# old_eagle_line_sensor.net
KiCad netlist of a schematic drawn in EAGLE
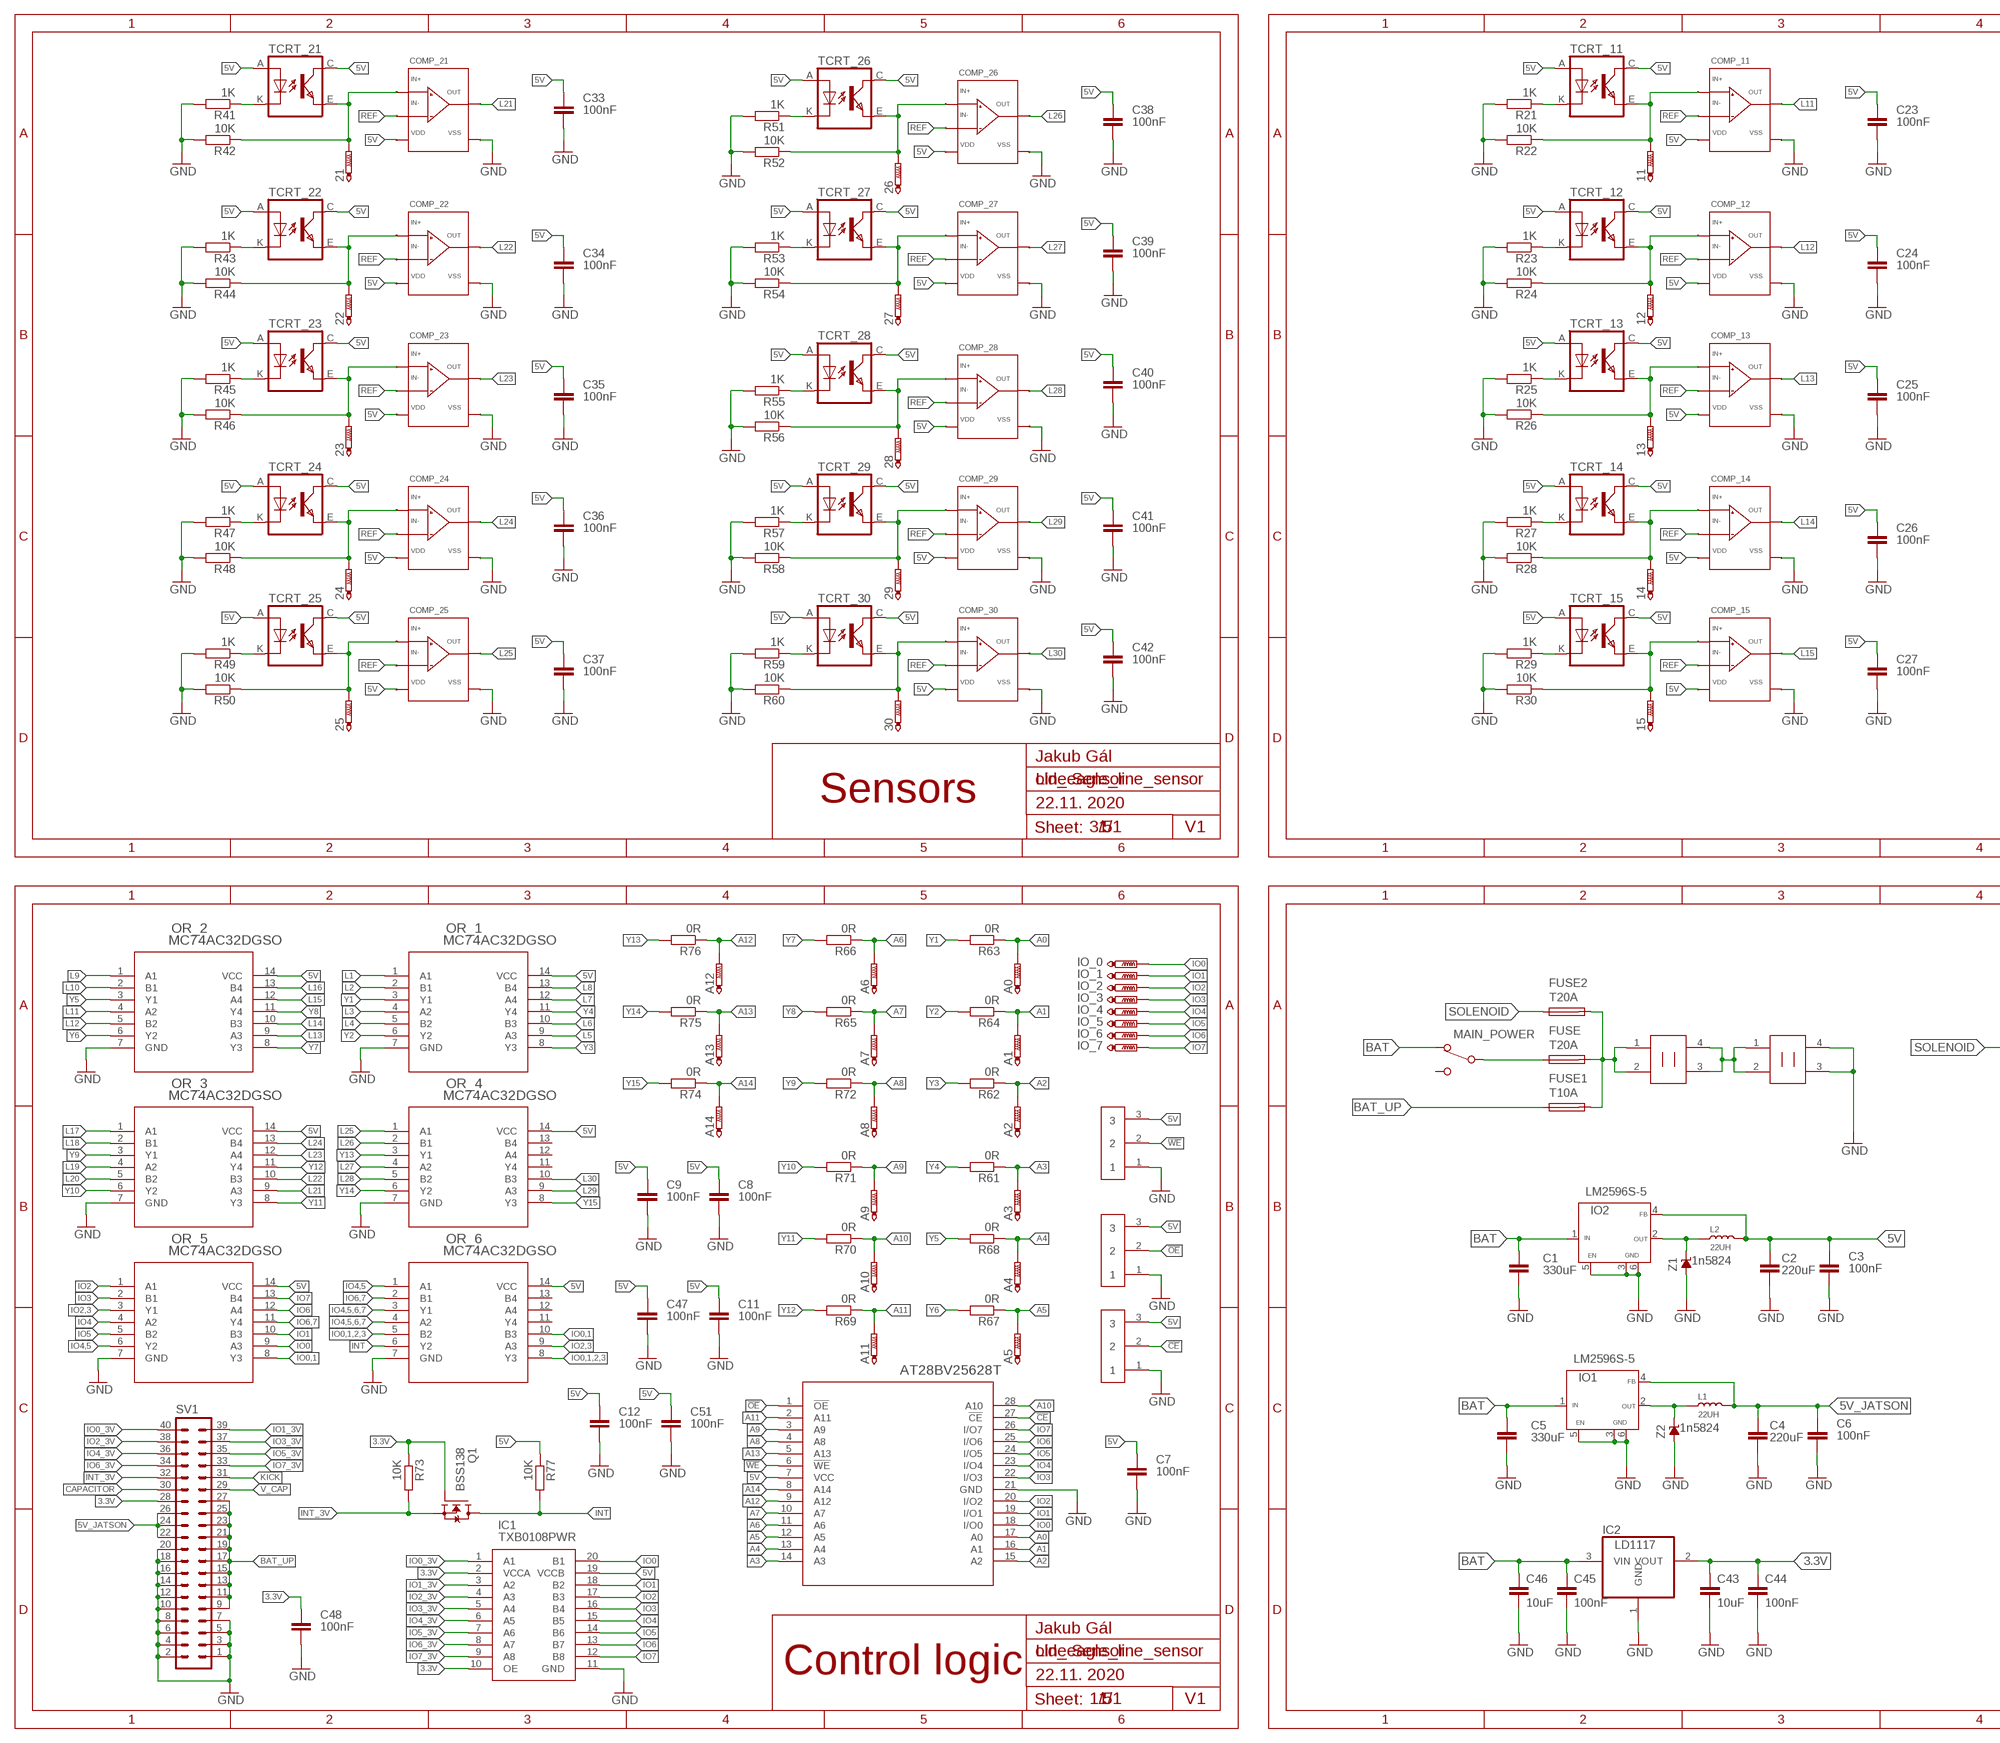
[diagram p0: schematic, sheet 1, part 1 of 2]
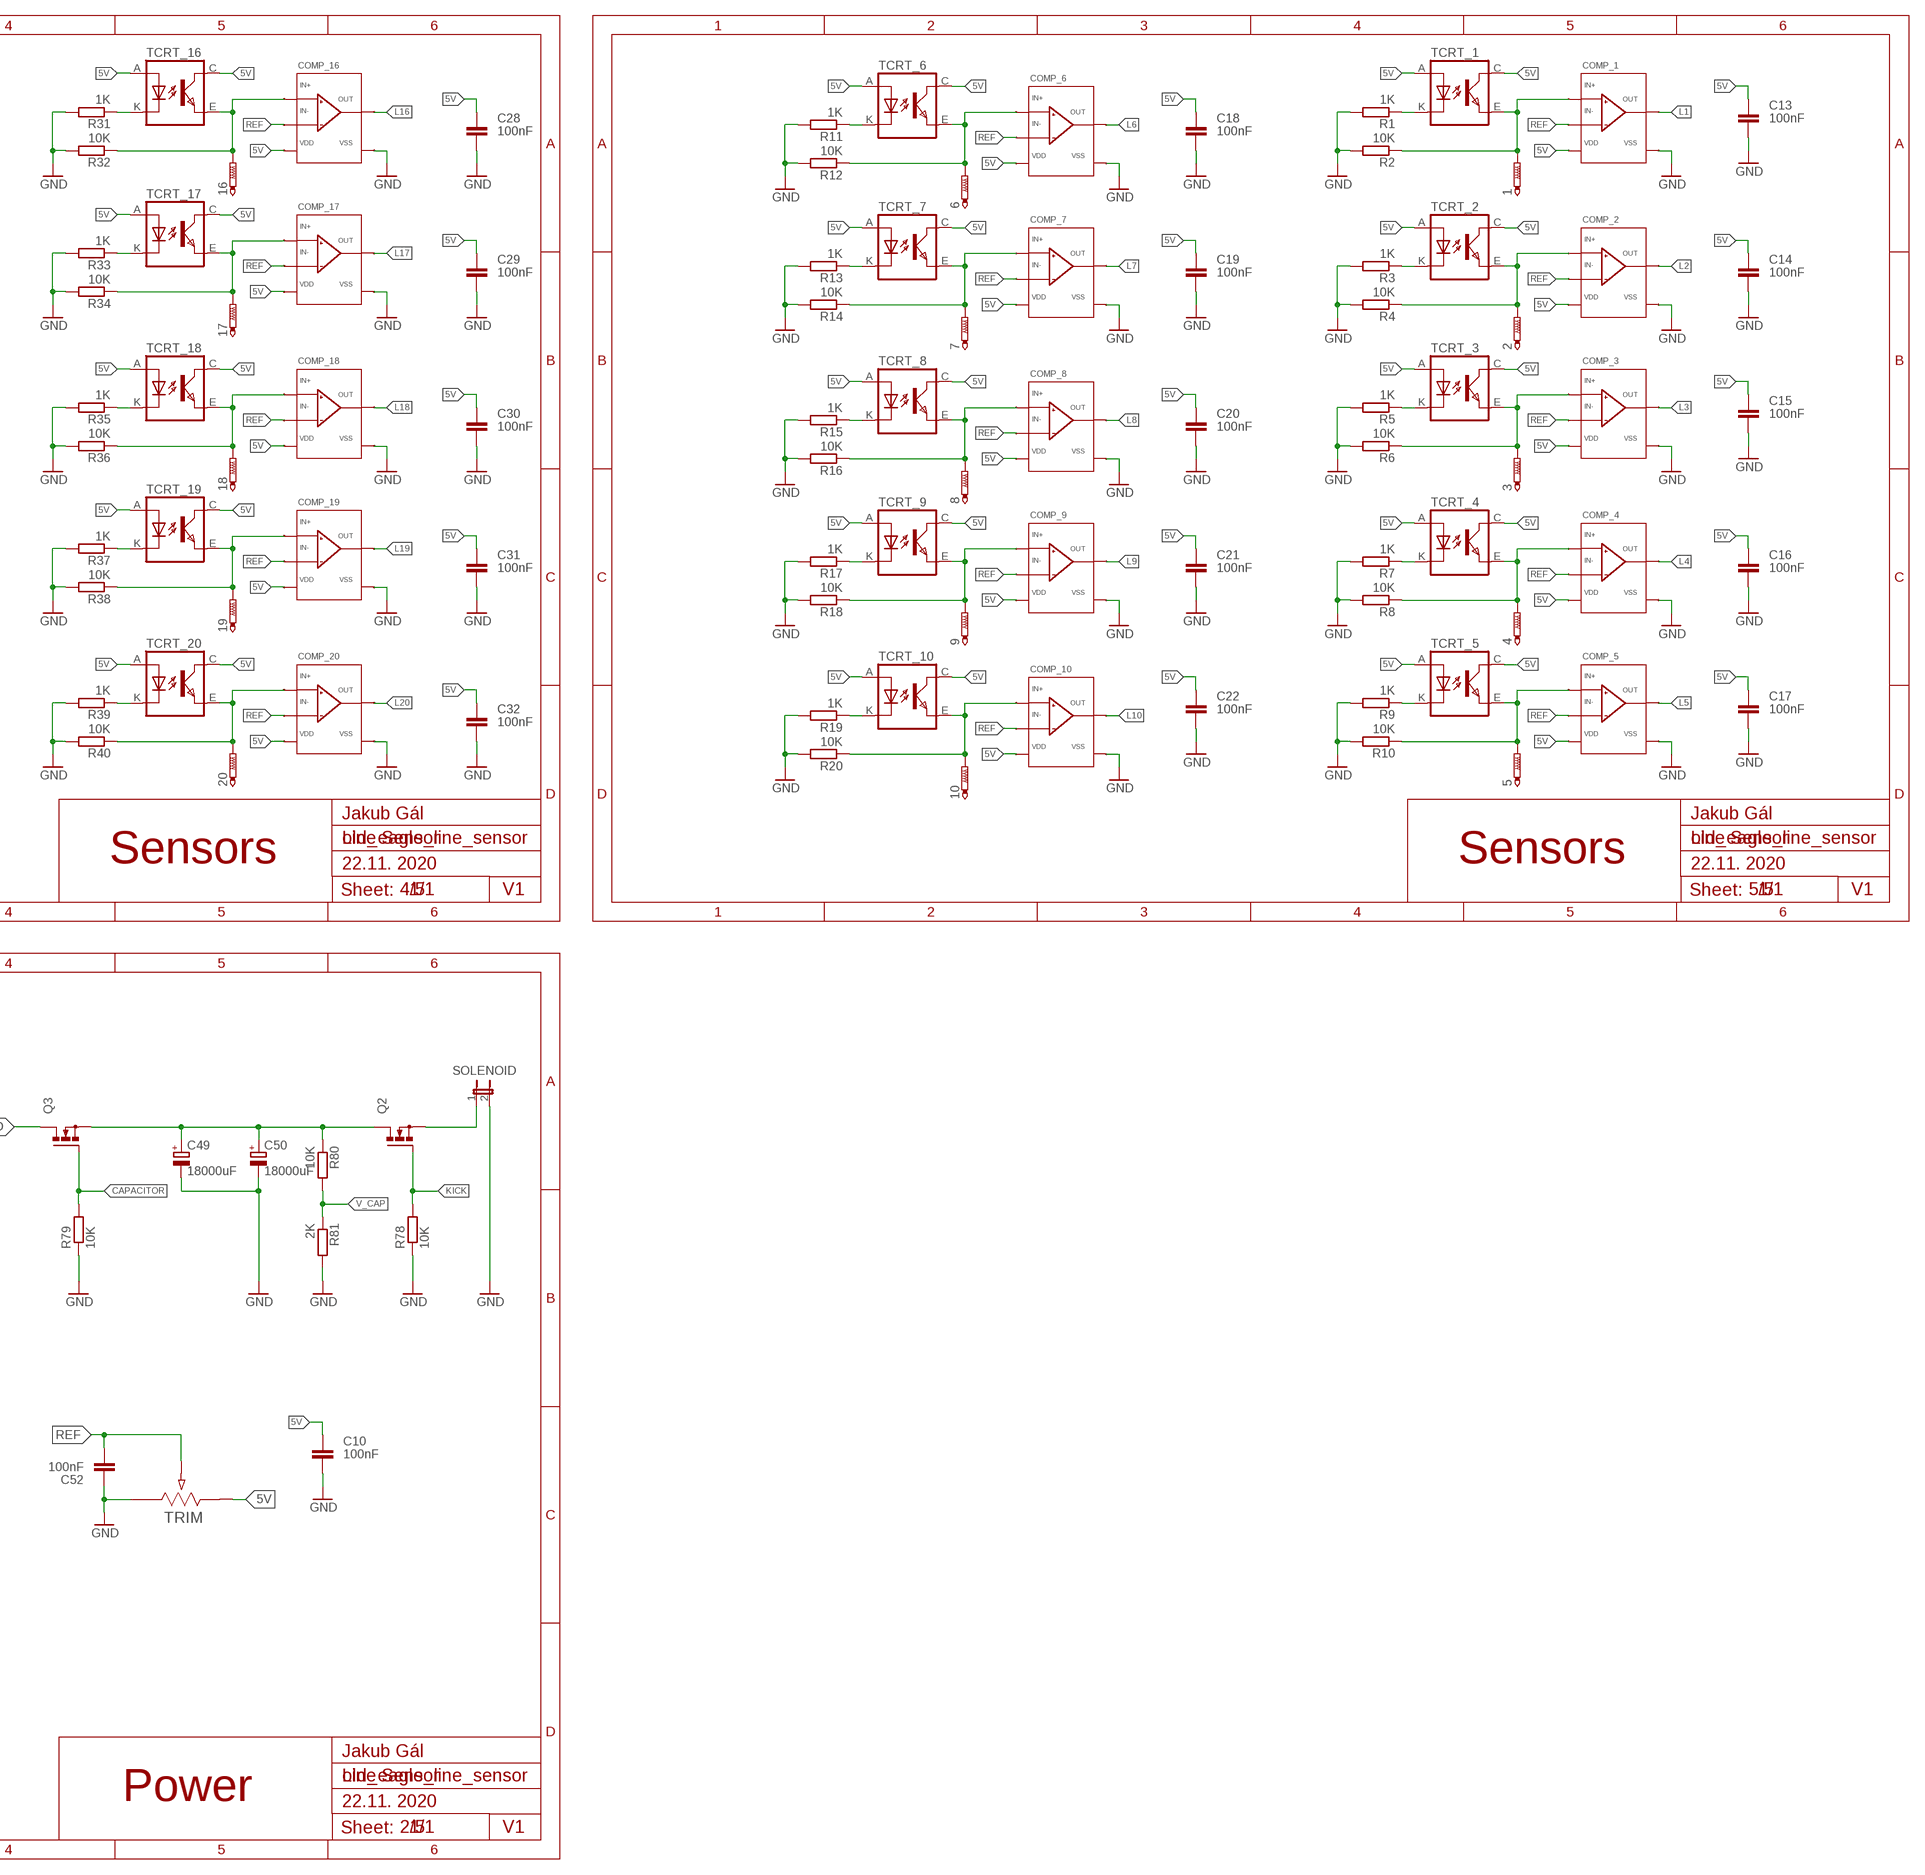
[diagram p1: schematic, sheet 1, part 2 of 2]

(export (version "E")
  (design (tool "Eeschema 10.0.6"))
  (components
    (comp (ref "!CE")
      (value "0603_S")
      (footprint "eagle-import:0603_S")
      (libsource (lib "eagle-import") (part "0603_S"))
    )
    (comp (ref "!OE")
      (value "0603_S")
      (footprint "eagle-import:0603_S")
      (libsource (lib "eagle-import") (part "0603_S"))
    )
    (comp (ref "!WE")
      (value "0603_S")
      (footprint "eagle-import:0603_S")
      (libsource (lib "eagle-import") (part "0603_S"))
    )
    (comp (ref "1")
      (value "PTR1TP20R")
      (footprint "eagle-import:TP20R")
      (libsource (lib "eagle-import") (part "PTR1TP20R"))
    )
    (comp (ref "2")
      (value "PTR1TP20R")
      (footprint "eagle-import:TP20R")
      (libsource (lib "eagle-import") (part "PTR1TP20R"))
    )
    (comp (ref "3")
      (value "PTR1TP20R")
      (footprint "eagle-import:TP20R")
      (libsource (lib "eagle-import") (part "PTR1TP20R"))
    )
    (comp (ref "4")
      (value "PTR1TP20R")
      (footprint "eagle-import:TP20R")
      (libsource (lib "eagle-import") (part "PTR1TP20R"))
    )
    (comp (ref "5")
      (value "PTR1TP20R")
      (footprint "eagle-import:TP20R")
      (libsource (lib "eagle-import") (part "PTR1TP20R"))
    )
    (comp (ref "6")
      (value "PTR1TP20R")
      (footprint "eagle-import:TP20R")
      (libsource (lib "eagle-import") (part "PTR1TP20R"))
    )
    (comp (ref "7")
      (value "PTR1TP20R")
      (footprint "eagle-import:TP20R")
      (libsource (lib "eagle-import") (part "PTR1TP20R"))
    )
    (comp (ref "8")
      (value "PTR1TP20R")
      (footprint "eagle-import:TP20R")
      (libsource (lib "eagle-import") (part "PTR1TP20R"))
    )
    (comp (ref "9")
      (value "PTR1TP20R")
      (footprint "eagle-import:TP20R")
      (libsource (lib "eagle-import") (part "PTR1TP20R"))
    )
    (comp (ref "10")
      (value "PTR1TP20R")
      (footprint "eagle-import:TP20R")
      (libsource (lib "eagle-import") (part "PTR1TP20R"))
    )
    (comp (ref "11")
      (value "PTR1TP20R")
      (footprint "eagle-import:TP20R")
      (libsource (lib "eagle-import") (part "PTR1TP20R"))
    )
    (comp (ref "12")
      (value "PTR1TP20R")
      (footprint "eagle-import:TP20R")
      (libsource (lib "eagle-import") (part "PTR1TP20R"))
    )
    (comp (ref "13")
      (value "PTR1TP20R")
      (footprint "eagle-import:TP20R")
      (libsource (lib "eagle-import") (part "PTR1TP20R"))
    )
    (comp (ref "14")
      (value "PTR1TP20R")
      (footprint "eagle-import:TP20R")
      (libsource (lib "eagle-import") (part "PTR1TP20R"))
    )
    (comp (ref "15")
      (value "PTR1TP20R")
      (footprint "eagle-import:TP20R")
      (libsource (lib "eagle-import") (part "PTR1TP20R"))
    )
    (comp (ref "16")
      (value "PTR1TP20R")
      (footprint "eagle-import:TP20R")
      (libsource (lib "eagle-import") (part "PTR1TP20R"))
    )
    (comp (ref "17")
      (value "PTR1TP20R")
      (footprint "eagle-import:TP20R")
      (libsource (lib "eagle-import") (part "PTR1TP20R"))
    )
    (comp (ref "18")
      (value "PTR1TP20R")
      (footprint "eagle-import:TP20R")
      (libsource (lib "eagle-import") (part "PTR1TP20R"))
    )
    (comp (ref "19")
      (value "PTR1TP20R")
      (footprint "eagle-import:TP20R")
      (libsource (lib "eagle-import") (part "PTR1TP20R"))
    )
    (comp (ref "20")
      (value "PTR1TP20R")
      (footprint "eagle-import:TP20R")
      (libsource (lib "eagle-import") (part "PTR1TP20R"))
    )
    (comp (ref "21")
      (value "PTR1TP20R")
      (footprint "eagle-import:TP20R")
      (libsource (lib "eagle-import") (part "PTR1TP20R"))
    )
    (comp (ref "22")
      (value "PTR1TP20R")
      (footprint "eagle-import:TP20R")
      (libsource (lib "eagle-import") (part "PTR1TP20R"))
    )
    (comp (ref "23")
      (value "PTR1TP20R")
      (footprint "eagle-import:TP20R")
      (libsource (lib "eagle-import") (part "PTR1TP20R"))
    )
    (comp (ref "24")
      (value "PTR1TP20R")
      (footprint "eagle-import:TP20R")
      (libsource (lib "eagle-import") (part "PTR1TP20R"))
    )
    (comp (ref "25")
      (value "PTR1TP20R")
      (footprint "eagle-import:TP20R")
      (libsource (lib "eagle-import") (part "PTR1TP20R"))
    )
    (comp (ref "26")
      (value "PTR1TP20R")
      (footprint "eagle-import:TP20R")
      (libsource (lib "eagle-import") (part "PTR1TP20R"))
    )
    (comp (ref "27")
      (value "PTR1TP20R")
      (footprint "eagle-import:TP20R")
      (libsource (lib "eagle-import") (part "PTR1TP20R"))
    )
    (comp (ref "28")
      (value "PTR1TP20R")
      (footprint "eagle-import:TP20R")
      (libsource (lib "eagle-import") (part "PTR1TP20R"))
    )
    (comp (ref "29")
      (value "PTR1TP20R")
      (footprint "eagle-import:TP20R")
      (libsource (lib "eagle-import") (part "PTR1TP20R"))
    )
    (comp (ref "30")
      (value "PTR1TP20R")
      (footprint "eagle-import:TP20R")
      (libsource (lib "eagle-import") (part "PTR1TP20R"))
    )
    (comp (ref "A0")
      (value "PTR1TP20R")
      (footprint "eagle-import:TP20R")
      (libsource (lib "eagle-import") (part "PTR1TP20R"))
    )
    (comp (ref "A1")
      (value "PTR1TP20R")
      (footprint "eagle-import:TP20R")
      (libsource (lib "eagle-import") (part "PTR1TP20R"))
    )
    (comp (ref "A2")
      (value "PTR1TP20R")
      (footprint "eagle-import:TP20R")
      (libsource (lib "eagle-import") (part "PTR1TP20R"))
    )
    (comp (ref "A3")
      (value "PTR1TP20R")
      (footprint "eagle-import:TP20R")
      (libsource (lib "eagle-import") (part "PTR1TP20R"))
    )
    (comp (ref "A4")
      (value "PTR1TP20R")
      (footprint "eagle-import:TP20R")
      (libsource (lib "eagle-import") (part "PTR1TP20R"))
    )
    (comp (ref "A5")
      (value "PTR1TP20R")
      (footprint "eagle-import:TP20R")
      (libsource (lib "eagle-import") (part "PTR1TP20R"))
    )
    (comp (ref "A6")
      (value "PTR1TP20R")
      (footprint "eagle-import:TP20R")
      (libsource (lib "eagle-import") (part "PTR1TP20R"))
    )
    (comp (ref "A7")
      (value "PTR1TP20R")
      (footprint "eagle-import:TP20R")
      (libsource (lib "eagle-import") (part "PTR1TP20R"))
    )
    (comp (ref "A8")
      (value "PTR1TP20R")
      (footprint "eagle-import:TP20R")
      (libsource (lib "eagle-import") (part "PTR1TP20R"))
    )
    (comp (ref "A9")
      (value "PTR1TP20R")
      (footprint "eagle-import:TP20R")
      (libsource (lib "eagle-import") (part "PTR1TP20R"))
    )
    (comp (ref "A10")
      (value "PTR1TP20R")
      (footprint "eagle-import:TP20R")
      (libsource (lib "eagle-import") (part "PTR1TP20R"))
    )
    (comp (ref "A11")
      (value "PTR1TP20R")
      (footprint "eagle-import:TP20R")
      (libsource (lib "eagle-import") (part "PTR1TP20R"))
    )
    (comp (ref "A12")
      (value "PTR1TP20R")
      (footprint "eagle-import:TP20R")
      (libsource (lib "eagle-import") (part "PTR1TP20R"))
    )
    (comp (ref "A13")
      (value "PTR1TP20R")
      (footprint "eagle-import:TP20R")
      (libsource (lib "eagle-import") (part "PTR1TP20R"))
    )
    (comp (ref "A14")
      (value "PTR1TP20R")
      (footprint "eagle-import:TP20R")
      (libsource (lib "eagle-import") (part "PTR1TP20R"))
    )
    (comp (ref "AT28BV25628T")
      (value "AT28BV25628T_ATM-M")
      (footprint "eagle-import:28T_ATM-M")
      (fields (field (name "MANUFACTURER_PART_NUMBER") "AT28BV256-20TU"))
      (libsource (lib "eagle-import") (part "AT28BV25628T_ATM-M"))
    )
    (comp (ref "C1")
      (value "330uF")
      (footprint "eagle-import:CAPM7343X310")
      (libsource (lib "eagle-import") (part "CTANTALUM-2917(7343-METRIC)_"))
    )
    (comp (ref "C2")
      (value "220uF")
      (footprint "eagle-import:CAPM7343X310")
      (libsource (lib "eagle-import") (part "CTANTALUM-2917(7343-METRIC)_"))
    )
    (comp (ref "C3")
      (value "100nF")
      (footprint "eagle-import:C0603")
      (libsource (lib "eagle-import") (part "C-EUC0603"))
    )
    (comp (ref "C4")
      (value "220uF")
      (footprint "eagle-import:CAPM7343X310")
      (libsource (lib "eagle-import") (part "CTANTALUM-2917(7343-METRIC)_"))
    )
    (comp (ref "C5")
      (value "330uF")
      (footprint "eagle-import:CAPM7343X310")
      (libsource (lib "eagle-import") (part "CTANTALUM-2917(7343-METRIC)_"))
    )
    (comp (ref "C6")
      (value "100nF")
      (footprint "eagle-import:C0603")
      (libsource (lib "eagle-import") (part "C-EUC0603"))
    )
    (comp (ref "C7")
      (value "100nF")
      (footprint "eagle-import:C0603")
      (libsource (lib "eagle-import") (part "C-EUC0603"))
    )
    (comp (ref "C8")
      (value "100nF")
      (footprint "eagle-import:C0603")
      (libsource (lib "eagle-import") (part "C-EUC0603"))
    )
    (comp (ref "C9")
      (value "100nF")
      (footprint "eagle-import:C0603")
      (libsource (lib "eagle-import") (part "C-EUC0603"))
    )
    (comp (ref "C10")
      (value "100nF")
      (footprint "eagle-import:C0603")
      (libsource (lib "eagle-import") (part "C-EUC0603"))
    )
    (comp (ref "C11")
      (value "100nF")
      (footprint "eagle-import:C0603")
      (libsource (lib "eagle-import") (part "C-EUC0603"))
    )
    (comp (ref "C12")
      (value "100nF")
      (footprint "eagle-import:C0603")
      (libsource (lib "eagle-import") (part "C-EUC0603"))
    )
    (comp (ref "C13")
      (value "100nF")
      (footprint "eagle-import:C0603")
      (libsource (lib "eagle-import") (part "C-EUC0603"))
    )
    (comp (ref "C14")
      (value "100nF")
      (footprint "eagle-import:C0603")
      (libsource (lib "eagle-import") (part "C-EUC0603"))
    )
    (comp (ref "C15")
      (value "100nF")
      (footprint "eagle-import:C0603")
      (libsource (lib "eagle-import") (part "C-EUC0603"))
    )
    (comp (ref "C16")
      (value "100nF")
      (footprint "eagle-import:C0603")
      (libsource (lib "eagle-import") (part "C-EUC0603"))
    )
    (comp (ref "C17")
      (value "100nF")
      (footprint "eagle-import:C0603")
      (libsource (lib "eagle-import") (part "C-EUC0603"))
    )
    (comp (ref "C18")
      (value "100nF")
      (footprint "eagle-import:C0603")
      (libsource (lib "eagle-import") (part "C-EUC0603"))
    )
    (comp (ref "C19")
      (value "100nF")
      (footprint "eagle-import:C0603")
      (libsource (lib "eagle-import") (part "C-EUC0603"))
    )
    (comp (ref "C20")
      (value "100nF")
      (footprint "eagle-import:C0603")
      (libsource (lib "eagle-import") (part "C-EUC0603"))
    )
    (comp (ref "C21")
      (value "100nF")
      (footprint "eagle-import:C0603")
      (libsource (lib "eagle-import") (part "C-EUC0603"))
    )
    (comp (ref "C22")
      (value "100nF")
      (footprint "eagle-import:C0603")
      (libsource (lib "eagle-import") (part "C-EUC0603"))
    )
    (comp (ref "C23")
      (value "100nF")
      (footprint "eagle-import:C0603")
      (libsource (lib "eagle-import") (part "C-EUC0603"))
    )
    (comp (ref "C24")
      (value "100nF")
      (footprint "eagle-import:C0603")
      (libsource (lib "eagle-import") (part "C-EUC0603"))
    )
    (comp (ref "C25")
      (value "100nF")
      (footprint "eagle-import:C0603")
      (libsource (lib "eagle-import") (part "C-EUC0603"))
    )
    (comp (ref "C26")
      (value "100nF")
      (footprint "eagle-import:C0603")
      (libsource (lib "eagle-import") (part "C-EUC0603"))
    )
    (comp (ref "C27")
      (value "100nF")
      (footprint "eagle-import:C0603")
      (libsource (lib "eagle-import") (part "C-EUC0603"))
    )
    (comp (ref "C28")
      (value "100nF")
      (footprint "eagle-import:C0603")
      (libsource (lib "eagle-import") (part "C-EUC0603"))
    )
    (comp (ref "C29")
      (value "100nF")
      (footprint "eagle-import:C0603")
      (libsource (lib "eagle-import") (part "C-EUC0603"))
    )
    (comp (ref "C30")
      (value "100nF")
      (footprint "eagle-import:C0603")
      (libsource (lib "eagle-import") (part "C-EUC0603"))
    )
    (comp (ref "C31")
      (value "100nF")
      (footprint "eagle-import:C0603")
      (libsource (lib "eagle-import") (part "C-EUC0603"))
    )
    (comp (ref "C32")
      (value "100nF")
      (footprint "eagle-import:C0603")
      (libsource (lib "eagle-import") (part "C-EUC0603"))
    )
    (comp (ref "C33")
      (value "100nF")
      (footprint "eagle-import:C0603")
      (libsource (lib "eagle-import") (part "C-EUC0603"))
    )
    (comp (ref "C34")
      (value "100nF")
      (footprint "eagle-import:C0603")
      (libsource (lib "eagle-import") (part "C-EUC0603"))
    )
    (comp (ref "C35")
      (value "100nF")
      (footprint "eagle-import:C0603")
      (libsource (lib "eagle-import") (part "C-EUC0603"))
    )
    (comp (ref "C36")
      (value "100nF")
      (footprint "eagle-import:C0603")
      (libsource (lib "eagle-import") (part "C-EUC0603"))
    )
    (comp (ref "C37")
      (value "100nF")
      (footprint "eagle-import:C0603")
      (libsource (lib "eagle-import") (part "C-EUC0603"))
    )
    (comp (ref "C38")
      (value "100nF")
      (footprint "eagle-import:C0603")
      (libsource (lib "eagle-import") (part "C-EUC0603"))
    )
    (comp (ref "C39")
      (value "100nF")
      (footprint "eagle-import:C0603")
      (libsource (lib "eagle-import") (part "C-EUC0603"))
    )
    (comp (ref "C40")
      (value "100nF")
      (footprint "eagle-import:C0603")
      (libsource (lib "eagle-import") (part "C-EUC0603"))
    )
    (comp (ref "C41")
      (value "100nF")
      (footprint "eagle-import:C0603")
      (libsource (lib "eagle-import") (part "C-EUC0603"))
    )
    (comp (ref "C42")
      (value "100nF")
      (footprint "eagle-import:C0603")
      (libsource (lib "eagle-import") (part "C-EUC0603"))
    )
    (comp (ref "C43")
      (value "10uF")
      (footprint "eagle-import:C0603")
      (libsource (lib "eagle-import") (part "C-EUC0603"))
    )
    (comp (ref "C44")
      (value "100nF")
      (footprint "eagle-import:C0603")
      (libsource (lib "eagle-import") (part "C-EUC0603"))
    )
    (comp (ref "C45")
      (value "100nF")
      (footprint "eagle-import:C0603")
      (libsource (lib "eagle-import") (part "C-EUC0603"))
    )
    (comp (ref "C46")
      (value "10uF")
      (footprint "eagle-import:C0603")
      (libsource (lib "eagle-import") (part "C-EUC0603"))
    )
    (comp (ref "C47")
      (value "100nF")
      (footprint "eagle-import:C0603")
      (libsource (lib "eagle-import") (part "C-EUC0603"))
    )
    (comp (ref "C48")
      (value "100nF")
      (footprint "eagle-import:C0603")
      (libsource (lib "eagle-import") (part "C-EUC0603"))
    )
    (comp (ref "C49")
      (value "18000uF")
      (footprint "eagle-import:EB30D")
      (libsource (lib "eagle-import") (part "CPOL-EUE10-30"))
    )
    (comp (ref "C50")
      (value "18000uF")
      (footprint "eagle-import:EB30D")
      (libsource (lib "eagle-import") (part "CPOL-EUE10-30"))
    )
    (comp (ref "C51")
      (value "100nF")
      (footprint "eagle-import:C0603")
      (libsource (lib "eagle-import") (part "C-EUC0603"))
    )
    (comp (ref "C52")
      (value "100nF")
      (footprint "eagle-import:C0603")
      (libsource (lib "eagle-import") (part "C-EUC0603"))
    )
    (comp (ref "COMP_1")
      (value "TC75S56FUTE85LF")
      (footprint "eagle-import:SOT-353___(USV)_TOS")
      (libsource (lib "eagle-import") (part "TC75S56FUTE85LF"))
    )
    (comp (ref "COMP_2")
      (value "TC75S56FUTE85LF")
      (footprint "eagle-import:SOT-353___(USV)_TOS")
      (libsource (lib "eagle-import") (part "TC75S56FUTE85LF"))
    )
    (comp (ref "COMP_3")
      (value "TC75S56FUTE85LF")
      (footprint "eagle-import:SOT-353___(USV)_TOS")
      (libsource (lib "eagle-import") (part "TC75S56FUTE85LF"))
    )
    (comp (ref "COMP_4")
      (value "TC75S56FUTE85LF")
      (footprint "eagle-import:SOT-353___(USV)_TOS")
      (libsource (lib "eagle-import") (part "TC75S56FUTE85LF"))
    )
    (comp (ref "COMP_5")
      (value "TC75S56FUTE85LF")
      (footprint "eagle-import:SOT-353___(USV)_TOS")
      (libsource (lib "eagle-import") (part "TC75S56FUTE85LF"))
    )
    (comp (ref "COMP_6")
      (value "TC75S56FUTE85LF")
      (footprint "eagle-import:SOT-353___(USV)_TOS")
      (libsource (lib "eagle-import") (part "TC75S56FUTE85LF"))
    )
    (comp (ref "COMP_7")
      (value "TC75S56FUTE85LF")
      (footprint "eagle-import:SOT-353___(USV)_TOS")
      (libsource (lib "eagle-import") (part "TC75S56FUTE85LF"))
    )
    (comp (ref "COMP_8")
      (value "TC75S56FUTE85LF")
      (footprint "eagle-import:SOT-353___(USV)_TOS")
      (libsource (lib "eagle-import") (part "TC75S56FUTE85LF"))
    )
    (comp (ref "COMP_9")
      (value "TC75S56FUTE85LF")
      (footprint "eagle-import:SOT-353___(USV)_TOS")
      (libsource (lib "eagle-import") (part "TC75S56FUTE85LF"))
    )
    (comp (ref "COMP_10")
      (value "TC75S56FUTE85LF")
      (footprint "eagle-import:SOT-353___(USV)_TOS")
      (libsource (lib "eagle-import") (part "TC75S56FUTE85LF"))
    )
    (comp (ref "COMP_11")
      (value "TC75S56FUTE85LF")
      (footprint "eagle-import:SOT-353___(USV)_TOS")
      (libsource (lib "eagle-import") (part "TC75S56FUTE85LF"))
    )
    (comp (ref "COMP_12")
      (value "TC75S56FUTE85LF")
      (footprint "eagle-import:SOT-353___(USV)_TOS")
      (libsource (lib "eagle-import") (part "TC75S56FUTE85LF"))
    )
    (comp (ref "COMP_13")
      (value "TC75S56FUTE85LF")
      (footprint "eagle-import:SOT-353___(USV)_TOS")
      (libsource (lib "eagle-import") (part "TC75S56FUTE85LF"))
    )
    (comp (ref "COMP_14")
      (value "TC75S56FUTE85LF")
      (footprint "eagle-import:SOT-353___(USV)_TOS")
      (libsource (lib "eagle-import") (part "TC75S56FUTE85LF"))
    )
    (comp (ref "COMP_15")
      (value "TC75S56FUTE85LF")
      (footprint "eagle-import:SOT-353___(USV)_TOS")
      (libsource (lib "eagle-import") (part "TC75S56FUTE85LF"))
    )
    (comp (ref "COMP_16")
      (value "TC75S56FUTE85LF")
      (footprint "eagle-import:SOT-353___(USV)_TOS")
      (libsource (lib "eagle-import") (part "TC75S56FUTE85LF"))
    )
    (comp (ref "COMP_17")
      (value "TC75S56FUTE85LF")
      (footprint "eagle-import:SOT-353___(USV)_TOS")
      (libsource (lib "eagle-import") (part "TC75S56FUTE85LF"))
    )
    (comp (ref "COMP_18")
      (value "TC75S56FUTE85LF")
      (footprint "eagle-import:SOT-353___(USV)_TOS")
      (libsource (lib "eagle-import") (part "TC75S56FUTE85LF"))
    )
    (comp (ref "COMP_19")
      (value "TC75S56FUTE85LF")
      (footprint "eagle-import:SOT-353___(USV)_TOS")
      (libsource (lib "eagle-import") (part "TC75S56FUTE85LF"))
    )
    (comp (ref "COMP_20")
      (value "TC75S56FUTE85LF")
      (footprint "eagle-import:SOT-353___(USV)_TOS")
      (libsource (lib "eagle-import") (part "TC75S56FUTE85LF"))
    )
    (comp (ref "COMP_21")
      (value "TC75S56FUTE85LF")
      (footprint "eagle-import:SOT-353___(USV)_TOS")
      (libsource (lib "eagle-import") (part "TC75S56FUTE85LF"))
    )
    (comp (ref "COMP_22")
      (value "TC75S56FUTE85LF")
      (footprint "eagle-import:SOT-353___(USV)_TOS")
      (libsource (lib "eagle-import") (part "TC75S56FUTE85LF"))
    )
    (comp (ref "COMP_23")
      (value "TC75S56FUTE85LF")
      (footprint "eagle-import:SOT-353___(USV)_TOS")
      (libsource (lib "eagle-import") (part "TC75S56FUTE85LF"))
    )
    (comp (ref "COMP_24")
      (value "TC75S56FUTE85LF")
      (footprint "eagle-import:SOT-353___(USV)_TOS")
      (libsource (lib "eagle-import") (part "TC75S56FUTE85LF"))
    )
    (comp (ref "COMP_25")
      (value "TC75S56FUTE85LF")
      (footprint "eagle-import:SOT-353___(USV)_TOS")
      (libsource (lib "eagle-import") (part "TC75S56FUTE85LF"))
    )
    (comp (ref "COMP_26")
      (value "TC75S56FUTE85LF")
      (footprint "eagle-import:SOT-353___(USV)_TOS")
      (libsource (lib "eagle-import") (part "TC75S56FUTE85LF"))
    )
    (comp (ref "COMP_27")
      (value "TC75S56FUTE85LF")
      (footprint "eagle-import:SOT-353___(USV)_TOS")
      (libsource (lib "eagle-import") (part "TC75S56FUTE85LF"))
    )
    (comp (ref "COMP_28")
      (value "TC75S56FUTE85LF")
      (footprint "eagle-import:SOT-353___(USV)_TOS")
      (libsource (lib "eagle-import") (part "TC75S56FUTE85LF"))
    )
    (comp (ref "COMP_29")
      (value "TC75S56FUTE85LF")
      (footprint "eagle-import:SOT-353___(USV)_TOS")
      (libsource (lib "eagle-import") (part "TC75S56FUTE85LF"))
    )
    (comp (ref "COMP_30")
      (value "TC75S56FUTE85LF")
      (footprint "eagle-import:SOT-353___(USV)_TOS")
      (libsource (lib "eagle-import") (part "TC75S56FUTE85LF"))
    )
    (comp (ref "FUSE")
      (value "T20A")
      (footprint "eagle-import:SH22,5A")
      (libsource (lib "eagle-import") (part "POISTKA2A"))
    )
    (comp (ref "FUSE1")
      (value "T10A")
      (footprint "eagle-import:SH22,5A")
      (libsource (lib "eagle-import") (part "POISTKA2A"))
    )
    (comp (ref "FUSE2")
      (value "T20A")
      (footprint "eagle-import:SH22,5A")
      (libsource (lib "eagle-import") (part "POISTKA2A"))
    )
    (comp (ref "IC1")
      (value "TXB0108PWR")
      (footprint "eagle-import:SOP65P640X120-20N")
      (fields (field (name "MOUSER_PART_NUMBER") "595-TXB0108PWR"))
      (libsource (lib "eagle-import") (part "TXB0108PWR"))
    )
    (comp (ref "IC2")
      (value "LD1117")
      (footprint "eagle-import:SOT223")
      (fields (field (name "MF") "TEXAS INSTRUMENTS") (field (name "MPN") "REG1117FAKTTT"))
      (libsource (lib "eagle-import") (part "LD1117"))
    )
    (comp (ref "IO1")
      (value "LM2596S-5")
      (footprint "eagle-import:TO263-5")
      (libsource (lib "eagle-import") (part "LM2596S"))
    )
    (comp (ref "IO2")
      (value "LM2596S-5")
      (footprint "eagle-import:TO263-5")
      (libsource (lib "eagle-import") (part "LM2596S"))
    )
    (comp (ref "IO_0")
      (value "PTR1TP20R")
      (footprint "eagle-import:TP20R")
      (libsource (lib "eagle-import") (part "PTR1TP20R"))
    )
    (comp (ref "IO_1")
      (value "PTR1TP20R")
      (footprint "eagle-import:TP20R")
      (libsource (lib "eagle-import") (part "PTR1TP20R"))
    )
    (comp (ref "IO_2")
      (value "PTR1TP20R")
      (footprint "eagle-import:TP20R")
      (libsource (lib "eagle-import") (part "PTR1TP20R"))
    )
    (comp (ref "IO_3")
      (value "PTR1TP20R")
      (footprint "eagle-import:TP20R")
      (libsource (lib "eagle-import") (part "PTR1TP20R"))
    )
    (comp (ref "IO_4")
      (value "PTR1TP20R")
      (footprint "eagle-import:TP20R")
      (libsource (lib "eagle-import") (part "PTR1TP20R"))
    )
    (comp (ref "IO_5")
      (value "PTR1TP20R")
      (footprint "eagle-import:TP20R")
      (libsource (lib "eagle-import") (part "PTR1TP20R"))
    )
    (comp (ref "IO_6")
      (value "PTR1TP20R")
      (footprint "eagle-import:TP20R")
      (libsource (lib "eagle-import") (part "PTR1TP20R"))
    )
    (comp (ref "IO_7")
      (value "PTR1TP20R")
      (footprint "eagle-import:TP20R")
      (libsource (lib "eagle-import") (part "PTR1TP20R"))
    )
    (comp (ref "L1")
      (value "22UH")
      (footprint "eagle-import:INDUCTOR_L0630")
      (libsource (lib "eagle-import") (part "INDUCTOR/FERRITE-BEAD0630"))
    )
    (comp (ref "L2")
      (value "22UH")
      (footprint "eagle-import:INDUCTOR_L0630")
      (libsource (lib "eagle-import") (part "INDUCTOR/FERRITE-BEAD0630"))
    )
    (comp (ref "MAIN_POWER")
      (value "PREP-1PB")
      (footprint "eagle-import:P-B069B")
      (libsource (lib "eagle-import") (part "PREP-1PB"))
    )
    (comp (ref "OR_1")
      (value "MC74AC32DGSO")
      (footprint "eagle-import:SOIC-14_NB_ONS-M")
      (fields
        (field (name "MANUFACTURER_PART_NUMBER") "MC74VHC32DR2G")
        (field (name "COPYRIGHT") "Copyright (C) 2016 Accelerated Designs. All rights reserved")
      )
      (libsource (lib "eagle-import") (part "MC74AC32DGSOIC-14_NB_ONS-M"))
    )
    (comp (ref "OR_2")
      (value "MC74AC32DGSO")
      (footprint "eagle-import:SOIC-14_NB_ONS-M")
      (fields
        (field (name "MANUFACTURER_PART_NUMBER") "MC74VHC32DR2G")
        (field (name "COPYRIGHT") "Copyright (C) 2016 Accelerated Designs. All rights reserved")
      )
      (libsource (lib "eagle-import") (part "MC74AC32DGSOIC-14_NB_ONS-M"))
    )
    (comp (ref "OR_3")
      (value "MC74AC32DGSO")
      (footprint "eagle-import:SOIC-14_NB_ONS-M")
      (fields
        (field (name "MANUFACTURER_PART_NUMBER") "MC74VHC32DR2G")
        (field (name "COPYRIGHT") "Copyright (C) 2016 Accelerated Designs. All rights reserved")
      )
      (libsource (lib "eagle-import") (part "MC74AC32DGSOIC-14_NB_ONS-M"))
    )
    (comp (ref "OR_4")
      (value "MC74AC32DGSO")
      (footprint "eagle-import:SOIC-14_NB_ONS-M")
      (fields
        (field (name "MANUFACTURER_PART_NUMBER") "MC74VHC32DR2G")
        (field (name "COPYRIGHT") "Copyright (C) 2016 Accelerated Designs. All rights reserved")
      )
      (libsource (lib "eagle-import") (part "MC74AC32DGSOIC-14_NB_ONS-M"))
    )
    (comp (ref "OR_5")
      (value "MC74AC32DGSO")
      (footprint "eagle-import:SOIC-14_NB_ONS-M")
      (fields
        (field (name "MANUFACTURER_PART_NUMBER") "MC74VHC32DR2G")
        (field (name "COPYRIGHT") "Copyright (C) 2016 Accelerated Designs. All rights reserved")
      )
      (libsource (lib "eagle-import") (part "MC74AC32DGSOIC-14_NB_ONS-M"))
    )
    (comp (ref "OR_6")
      (value "MC74AC32DGSO")
      (footprint "eagle-import:SOIC-14_NB_ONS-M")
      (fields
        (field (name "MANUFACTURER_PART_NUMBER") "MC74VHC32DR2G")
        (field (name "COPYRIGHT") "Copyright (C) 2016 Accelerated Designs. All rights reserved")
      )
      (libsource (lib "eagle-import") (part "MC74AC32DGSOIC-14_NB_ONS-M"))
    )
    (comp (ref "Q1")
      (value "BSS138")
      (footprint "eagle-import:SOT23")
      (fields (field (name "MF") "Fairchild"))
      (libsource (lib "eagle-import") (part "BSS138"))
    )
    (comp (ref "Q2")
      (value "PMOSFET_NTO220BV")
      (footprint "eagle-import:TO220BV")
      (libsource (lib "eagle-import") (part "PMOSFET_NTO220BV"))
    )
    (comp (ref "Q3")
      (value "PMOSFET_NTO220BV")
      (footprint "eagle-import:TO220BV")
      (libsource (lib "eagle-import") (part "PMOSFET_NTO220BV"))
    )
    (comp (ref "R1")
      (value "1K")
      (footprint "eagle-import:R0603")
      (libsource (lib "eagle-import") (part "R-EU_R0603"))
    )
    (comp (ref "R2")
      (value "10K")
      (footprint "eagle-import:R0603")
      (libsource (lib "eagle-import") (part "R-EU_R0603"))
    )
    (comp (ref "R3")
      (value "1K")
      (footprint "eagle-import:R0603")
      (libsource (lib "eagle-import") (part "R-EU_R0603"))
    )
    (comp (ref "R4")
      (value "10K")
      (footprint "eagle-import:R0603")
      (libsource (lib "eagle-import") (part "R-EU_R0603"))
    )
    (comp (ref "R5")
      (value "1K")
      (footprint "eagle-import:R0603")
      (libsource (lib "eagle-import") (part "R-EU_R0603"))
    )
    (comp (ref "R6")
      (value "10K")
      (footprint "eagle-import:R0603")
      (libsource (lib "eagle-import") (part "R-EU_R0603"))
    )
    (comp (ref "R7")
      (value "1K")
      (footprint "eagle-import:R0603")
      (libsource (lib "eagle-import") (part "R-EU_R0603"))
    )
    (comp (ref "R8")
      (value "10K")
      (footprint "eagle-import:R0603")
      (libsource (lib "eagle-import") (part "R-EU_R0603"))
    )
    (comp (ref "R9")
      (value "1K")
      (footprint "eagle-import:R0603")
      (libsource (lib "eagle-import") (part "R-EU_R0603"))
    )
    (comp (ref "R10")
      (value "10K")
      (footprint "eagle-import:R0603")
      (libsource (lib "eagle-import") (part "R-EU_R0603"))
    )
    (comp (ref "R11")
      (value "1K")
      (footprint "eagle-import:R0603")
      (libsource (lib "eagle-import") (part "R-EU_R0603"))
    )
    (comp (ref "R12")
      (value "10K")
      (footprint "eagle-import:R0603")
      (libsource (lib "eagle-import") (part "R-EU_R0603"))
    )
    (comp (ref "R13")
      (value "1K")
      (footprint "eagle-import:R0603")
      (libsource (lib "eagle-import") (part "R-EU_R0603"))
    )
    (comp (ref "R14")
      (value "10K")
      (footprint "eagle-import:R0603")
      (libsource (lib "eagle-import") (part "R-EU_R0603"))
    )
    (comp (ref "R15")
      (value "1K")
      (footprint "eagle-import:R0603")
      (libsource (lib "eagle-import") (part "R-EU_R0603"))
    )
    (comp (ref "R16")
      (value "10K")
      (footprint "eagle-import:R0603")
      (libsource (lib "eagle-import") (part "R-EU_R0603"))
    )
    (comp (ref "R17")
      (value "1K")
      (footprint "eagle-import:R0603")
      (libsource (lib "eagle-import") (part "R-EU_R0603"))
    )
    (comp (ref "R18")
      (value "10K")
      (footprint "eagle-import:R0603")
      (libsource (lib "eagle-import") (part "R-EU_R0603"))
    )
    (comp (ref "R19")
      (value "1K")
      (footprint "eagle-import:R0603")
      (libsource (lib "eagle-import") (part "R-EU_R0603"))
    )
    (comp (ref "R20")
      (value "10K")
      (footprint "eagle-import:R0603")
      (libsource (lib "eagle-import") (part "R-EU_R0603"))
    )
    (comp (ref "R21")
      (value "1K")
      (footprint "eagle-import:R0603")
      (libsource (lib "eagle-import") (part "R-EU_R0603"))
    )
    (comp (ref "R22")
      (value "10K")
      (footprint "eagle-import:R0603")
      (libsource (lib "eagle-import") (part "R-EU_R0603"))
    )
    (comp (ref "R23")
      (value "1K")
      (footprint "eagle-import:R0603")
      (libsource (lib "eagle-import") (part "R-EU_R0603"))
    )
    (comp (ref "R24")
      (value "10K")
      (footprint "eagle-import:R0603")
      (libsource (lib "eagle-import") (part "R-EU_R0603"))
    )
    (comp (ref "R25")
      (value "1K")
      (footprint "eagle-import:R0603")
      (libsource (lib "eagle-import") (part "R-EU_R0603"))
    )
    (comp (ref "R26")
      (value "10K")
      (footprint "eagle-import:R0603")
      (libsource (lib "eagle-import") (part "R-EU_R0603"))
    )
    (comp (ref "R27")
      (value "1K")
      (footprint "eagle-import:R0603")
      (libsource (lib "eagle-import") (part "R-EU_R0603"))
    )
    (comp (ref "R28")
      (value "10K")
      (footprint "eagle-import:R0603")
      (libsource (lib "eagle-import") (part "R-EU_R0603"))
    )
    (comp (ref "R29")
      (value "1K")
      (footprint "eagle-import:R0603")
      (libsource (lib "eagle-import") (part "R-EU_R0603"))
    )
    (comp (ref "R30")
      (value "10K")
      (footprint "eagle-import:R0603")
      (libsource (lib "eagle-import") (part "R-EU_R0603"))
    )
    (comp (ref "R31")
      (value "1K")
      (footprint "eagle-import:R0603")
      (libsource (lib "eagle-import") (part "R-EU_R0603"))
    )
    (comp (ref "R32")
      (value "10K")
      (footprint "eagle-import:R0603")
      (libsource (lib "eagle-import") (part "R-EU_R0603"))
    )
    (comp (ref "R33")
      (value "1K")
      (footprint "eagle-import:R0603")
      (libsource (lib "eagle-import") (part "R-EU_R0603"))
    )
    (comp (ref "R34")
      (value "10K")
      (footprint "eagle-import:R0603")
      (libsource (lib "eagle-import") (part "R-EU_R0603"))
    )
    (comp (ref "R35")
      (value "1K")
      (footprint "eagle-import:R0603")
      (libsource (lib "eagle-import") (part "R-EU_R0603"))
    )
    (comp (ref "R36")
      (value "10K")
      (footprint "eagle-import:R0603")
      (libsource (lib "eagle-import") (part "R-EU_R0603"))
    )
    (comp (ref "R37")
      (value "1K")
      (footprint "eagle-import:R0603")
      (libsource (lib "eagle-import") (part "R-EU_R0603"))
    )
    (comp (ref "R38")
      (value "10K")
      (footprint "eagle-import:R0603")
      (libsource (lib "eagle-import") (part "R-EU_R0603"))
    )
    (comp (ref "R39")
      (value "1K")
      (footprint "eagle-import:R0603")
      (libsource (lib "eagle-import") (part "R-EU_R0603"))
    )
    (comp (ref "R40")
      (value "10K")
      (footprint "eagle-import:R0603")
      (libsource (lib "eagle-import") (part "R-EU_R0603"))
    )
    (comp (ref "R41")
      (value "1K")
      (footprint "eagle-import:R0603")
      (libsource (lib "eagle-import") (part "R-EU_R0603"))
    )
    (comp (ref "R42")
      (value "10K")
      (footprint "eagle-import:R0603")
      (libsource (lib "eagle-import") (part "R-EU_R0603"))
    )
    (comp (ref "R43")
      (value "1K")
      (footprint "eagle-import:R0603")
      (libsource (lib "eagle-import") (part "R-EU_R0603"))
    )
    (comp (ref "R44")
      (value "10K")
      (footprint "eagle-import:R0603")
      (libsource (lib "eagle-import") (part "R-EU_R0603"))
    )
    (comp (ref "R45")
      (value "1K")
      (footprint "eagle-import:R0603")
      (libsource (lib "eagle-import") (part "R-EU_R0603"))
    )
    (comp (ref "R46")
      (value "10K")
      (footprint "eagle-import:R0603")
      (libsource (lib "eagle-import") (part "R-EU_R0603"))
    )
    (comp (ref "R47")
      (value "1K")
      (footprint "eagle-import:R0603")
      (libsource (lib "eagle-import") (part "R-EU_R0603"))
    )
    (comp (ref "R48")
      (value "10K")
      (footprint "eagle-import:R0603")
      (libsource (lib "eagle-import") (part "R-EU_R0603"))
    )
    (comp (ref "R49")
      (value "1K")
      (footprint "eagle-import:R0603")
      (libsource (lib "eagle-import") (part "R-EU_R0603"))
    )
    (comp (ref "R50")
      (value "10K")
      (footprint "eagle-import:R0603")
      (libsource (lib "eagle-import") (part "R-EU_R0603"))
    )
    (comp (ref "R51")
      (value "1K")
      (footprint "eagle-import:R0603")
      (libsource (lib "eagle-import") (part "R-EU_R0603"))
    )
    (comp (ref "R52")
      (value "10K")
      (footprint "eagle-import:R0603")
      (libsource (lib "eagle-import") (part "R-EU_R0603"))
    )
    (comp (ref "R53")
      (value "1K")
      (footprint "eagle-import:R0603")
      (libsource (lib "eagle-import") (part "R-EU_R0603"))
    )
    (comp (ref "R54")
      (value "10K")
      (footprint "eagle-import:R0603")
      (libsource (lib "eagle-import") (part "R-EU_R0603"))
    )
    (comp (ref "R55")
      (value "1K")
      (footprint "eagle-import:R0603")
      (libsource (lib "eagle-import") (part "R-EU_R0603"))
    )
    (comp (ref "R56")
      (value "10K")
      (footprint "eagle-import:R0603")
      (libsource (lib "eagle-import") (part "R-EU_R0603"))
    )
    (comp (ref "R57")
      (value "1K")
      (footprint "eagle-import:R0603")
      (libsource (lib "eagle-import") (part "R-EU_R0603"))
    )
    (comp (ref "R58")
      (value "10K")
      (footprint "eagle-import:R0603")
      (libsource (lib "eagle-import") (part "R-EU_R0603"))
    )
    (comp (ref "R59")
      (value "1K")
      (footprint "eagle-import:R0603")
      (libsource (lib "eagle-import") (part "R-EU_R0603"))
    )
    (comp (ref "R60")
      (value "10K")
      (footprint "eagle-import:R0603")
      (libsource (lib "eagle-import") (part "R-EU_R0603"))
    )
    (comp (ref "R61")
      (value "0R")
      (footprint "eagle-import:R0603")
      (libsource (lib "eagle-import") (part "R-EU_R0603"))
    )
    (comp (ref "R62")
      (value "0R")
      (footprint "eagle-import:R0603")
      (libsource (lib "eagle-import") (part "R-EU_R0603"))
    )
    (comp (ref "R63")
      (value "0R")
      (footprint "eagle-import:R0603")
      (libsource (lib "eagle-import") (part "R-EU_R0603"))
    )
    (comp (ref "R64")
      (value "0R")
      (footprint "eagle-import:R0603")
      (libsource (lib "eagle-import") (part "R-EU_R0603"))
    )
    (comp (ref "R65")
      (value "0R")
      (footprint "eagle-import:R0603")
      (libsource (lib "eagle-import") (part "R-EU_R0603"))
    )
    (comp (ref "R66")
      (value "0R")
      (footprint "eagle-import:R0603")
      (libsource (lib "eagle-import") (part "R-EU_R0603"))
    )
    (comp (ref "R67")
      (value "0R")
      (footprint "eagle-import:R0603")
      (libsource (lib "eagle-import") (part "R-EU_R0603"))
    )
    (comp (ref "R68")
      (value "0R")
      (footprint "eagle-import:R0603")
      (libsource (lib "eagle-import") (part "R-EU_R0603"))
    )
    (comp (ref "R69")
      (value "0R")
      (footprint "eagle-import:R0603")
      (libsource (lib "eagle-import") (part "R-EU_R0603"))
    )
    (comp (ref "R70")
      (value "0R")
      (footprint "eagle-import:R0603")
      (libsource (lib "eagle-import") (part "R-EU_R0603"))
    )
    (comp (ref "R71")
      (value "0R")
      (footprint "eagle-import:R0603")
      (libsource (lib "eagle-import") (part "R-EU_R0603"))
    )
    (comp (ref "R72")
      (value "0R")
      (footprint "eagle-import:R0603")
      (libsource (lib "eagle-import") (part "R-EU_R0603"))
    )
    (comp (ref "R73")
      (value "10K")
      (footprint "eagle-import:R0603")
      (libsource (lib "eagle-import") (part "R-EU_R0603"))
    )
    (comp (ref "R74")
      (value "0R")
      (footprint "eagle-import:R0603")
      (libsource (lib "eagle-import") (part "R-EU_R0603"))
    )
    (comp (ref "R75")
      (value "0R")
      (footprint "eagle-import:R0603")
      (libsource (lib "eagle-import") (part "R-EU_R0603"))
    )
    (comp (ref "R76")
      (value "0R")
      (footprint "eagle-import:R0603")
      (libsource (lib "eagle-import") (part "R-EU_R0603"))
    )
    (comp (ref "R77")
      (value "10K")
      (footprint "eagle-import:R0603")
      (libsource (lib "eagle-import") (part "R-EU_R0603"))
    )
    (comp (ref "R78")
      (value "10K")
      (footprint "eagle-import:R1206")
      (libsource (lib "eagle-import") (part "R-EU_R1206"))
    )
    (comp (ref "R79")
      (value "10K")
      (footprint "eagle-import:R1206")
      (libsource (lib "eagle-import") (part "R-EU_R1206"))
    )
    (comp (ref "R80")
      (value "10K")
      (footprint "eagle-import:R0603")
      (libsource (lib "eagle-import") (part "R-EU_R0603"))
    )
    (comp (ref "R81")
      (value "2K")
      (footprint "eagle-import:R0603")
      (libsource (lib "eagle-import") (part "R-EU_R0603"))
    )
    (comp (ref "SOLENOID")
      (value "JP1E")
      (footprint "eagle-import:JP1")
      (libsource (lib "eagle-import") (part "JP1E"))
    )
    (comp (ref "SV1")
      (value "MLW40")
      (footprint "eagle-import:ML40")
      (libsource (lib "eagle-import") (part "MLW40"))
    )
    (comp (ref "TCRT_1")
      (value "TCRT5000")
      (footprint "eagle-import:TCRT5000")
      (libsource (lib "eagle-import") (part "TCRT5000"))
    )
    (comp (ref "TCRT_2")
      (value "TCRT5000")
      (footprint "eagle-import:TCRT5000")
      (libsource (lib "eagle-import") (part "TCRT5000"))
    )
    (comp (ref "TCRT_3")
      (value "TCRT5000")
      (footprint "eagle-import:TCRT5000")
      (libsource (lib "eagle-import") (part "TCRT5000"))
    )
    (comp (ref "TCRT_4")
      (value "TCRT5000")
      (footprint "eagle-import:TCRT5000")
      (libsource (lib "eagle-import") (part "TCRT5000"))
    )
    (comp (ref "TCRT_5")
      (value "TCRT5000")
      (footprint "eagle-import:TCRT5000")
      (libsource (lib "eagle-import") (part "TCRT5000"))
    )
    (comp (ref "TCRT_6")
      (value "TCRT5000")
      (footprint "eagle-import:TCRT5000")
      (libsource (lib "eagle-import") (part "TCRT5000"))
    )
    (comp (ref "TCRT_7")
      (value "TCRT5000")
      (footprint "eagle-import:TCRT5000")
      (libsource (lib "eagle-import") (part "TCRT5000"))
    )
    (comp (ref "TCRT_8")
      (value "TCRT5000")
      (footprint "eagle-import:TCRT5000")
      (libsource (lib "eagle-import") (part "TCRT5000"))
    )
    (comp (ref "TCRT_9")
      (value "TCRT5000")
      (footprint "eagle-import:TCRT5000")
      (libsource (lib "eagle-import") (part "TCRT5000"))
    )
    (comp (ref "TCRT_10")
      (value "TCRT5000")
      (footprint "eagle-import:TCRT5000")
      (libsource (lib "eagle-import") (part "TCRT5000"))
    )
    (comp (ref "TCRT_11")
      (value "TCRT5000")
      (footprint "eagle-import:TCRT5000")
      (libsource (lib "eagle-import") (part "TCRT5000"))
    )
    (comp (ref "TCRT_12")
      (value "TCRT5000")
      (footprint "eagle-import:TCRT5000")
      (libsource (lib "eagle-import") (part "TCRT5000"))
    )
    (comp (ref "TCRT_13")
      (value "TCRT5000")
      (footprint "eagle-import:TCRT5000")
      (libsource (lib "eagle-import") (part "TCRT5000"))
    )
    (comp (ref "TCRT_14")
      (value "TCRT5000")
      (footprint "eagle-import:TCRT5000")
      (libsource (lib "eagle-import") (part "TCRT5000"))
    )
    (comp (ref "TCRT_15")
      (value "TCRT5000")
      (footprint "eagle-import:TCRT5000")
      (libsource (lib "eagle-import") (part "TCRT5000"))
    )
    (comp (ref "TCRT_16")
      (value "TCRT5000")
      (footprint "eagle-import:TCRT5000")
      (libsource (lib "eagle-import") (part "TCRT5000"))
    )
    (comp (ref "TCRT_17")
      (value "TCRT5000")
      (footprint "eagle-import:TCRT5000")
      (libsource (lib "eagle-import") (part "TCRT5000"))
    )
    (comp (ref "TCRT_18")
      (value "TCRT5000")
      (footprint "eagle-import:TCRT5000")
      (libsource (lib "eagle-import") (part "TCRT5000"))
    )
    (comp (ref "TCRT_19")
      (value "TCRT5000")
      (footprint "eagle-import:TCRT5000")
      (libsource (lib "eagle-import") (part "TCRT5000"))
    )
    (comp (ref "TCRT_20")
      (value "TCRT5000")
      (footprint "eagle-import:TCRT5000")
      (libsource (lib "eagle-import") (part "TCRT5000"))
    )
    (comp (ref "TCRT_21")
      (value "TCRT5000")
      (footprint "eagle-import:TCRT5000")
      (libsource (lib "eagle-import") (part "TCRT5000"))
    )
    (comp (ref "TCRT_22")
      (value "TCRT5000")
      (footprint "eagle-import:TCRT5000")
      (libsource (lib "eagle-import") (part "TCRT5000"))
    )
    (comp (ref "TCRT_23")
      (value "TCRT5000")
      (footprint "eagle-import:TCRT5000")
      (libsource (lib "eagle-import") (part "TCRT5000"))
    )
    (comp (ref "TCRT_24")
      (value "TCRT5000")
      (footprint "eagle-import:TCRT5000")
      (libsource (lib "eagle-import") (part "TCRT5000"))
    )
    (comp (ref "TCRT_25")
      (value "TCRT5000")
      (footprint "eagle-import:TCRT5000")
      (libsource (lib "eagle-import") (part "TCRT5000"))
    )
    (comp (ref "TCRT_26")
      (value "TCRT5000")
      (footprint "eagle-import:TCRT5000")
      (libsource (lib "eagle-import") (part "TCRT5000"))
    )
    (comp (ref "TCRT_27")
      (value "TCRT5000")
      (footprint "eagle-import:TCRT5000")
      (libsource (lib "eagle-import") (part "TCRT5000"))
    )
    (comp (ref "TCRT_28")
      (value "TCRT5000")
      (footprint "eagle-import:TCRT5000")
      (libsource (lib "eagle-import") (part "TCRT5000"))
    )
    (comp (ref "TCRT_29")
      (value "TCRT5000")
      (footprint "eagle-import:TCRT5000")
      (libsource (lib "eagle-import") (part "TCRT5000"))
    )
    (comp (ref "TCRT_30")
      (value "TCRT5000")
      (footprint "eagle-import:TCRT5000")
      (libsource (lib "eagle-import") (part "TCRT5000"))
    )
    (comp (ref "TRIM")
      (value "3362W-1-103LF")
      (footprint "eagle-import:POT_3362W")
      (libsource (lib "eagle-import") (part "3362W-1-103LF"))
    )
    (comp (ref "U$4")
      (value "TERMINAL")
      (footprint "eagle-import:TERMINAL")
      (libsource (lib "eagle-import") (part "TERMINAL"))
    )
    (comp (ref "U$5")
      (value "TERMINAL")
      (footprint "eagle-import:TERMINAL")
      (libsource (lib "eagle-import") (part "TERMINAL"))
    )
    (comp (ref "Z1")
      (value "1n5824")
      (footprint "eagle-import:SUPRESSOR_SMAJ")
      (libsource (lib "eagle-import") (part "SUPRESSOR_TVS-UD-SMAJ"))
    )
    (comp (ref "Z2")
      (value "1n5824")
      (footprint "eagle-import:SUPRESSOR_SMAJ")
      (libsource (lib "eagle-import") (part "SUPRESSOR_TVS-UD-SMAJ"))
    )
  )
  (nets
    (net (code "1") (name "/~{CE}") (class "Default")
      (node (ref "!CE") (pin "2") (pinfunction "A2_2") (pintype "bidirectional"))
      (node (ref "AT28BV25628T") (pin "27") (pinfunction "~{CE}_27") (pintype "passive"))
    )
    (net (code "2") (name "/~{OE}") (class "Default")
      (node (ref "!OE") (pin "2") (pinfunction "A2_2") (pintype "bidirectional"))
      (node (ref "AT28BV25628T") (pin "1") (pinfunction "~{OE}_1") (pintype "output"))
    )
    (net (code "3") (name "/~{WE}") (class "Default")
      (node (ref "!WE") (pin "2") (pinfunction "A2_2") (pintype "bidirectional"))
      (node (ref "AT28BV25628T") (pin "6") (pinfunction "~{WE}_6") (pintype "passive"))
    )
    (net (code "4") (name "3.3V") (class "Default")
      (node (ref "C43") (pin "1") (pinfunction "1_1") (pintype "passive"))
      (node (ref "C44") (pin "1") (pinfunction "1_1") (pintype "passive"))
      (node (ref "C48") (pin "1") (pinfunction "1_1") (pintype "passive"))
      (node (ref "IC1") (pin "10") (pinfunction "OE_10") (pintype "bidirectional"))
      (node (ref "IC1") (pin "2") (pinfunction "VCCA_2") (pintype "bidirectional"))
      (node (ref "IC2") (pin "2") (pinfunction "VOUT_2") (pintype "output"))
      (node (ref "Q1") (pin "1") (pinfunction "G_1") (pintype "passive"))
      (node (ref "R73") (pin "1") (pinfunction "1_1") (pintype "passive"))
      (node (ref "SV1") (pin "28") (pinfunction "28_28") (pintype "passive"))
    )
    (net (code "5") (name "5V") (class "Default")
      (node (ref "!CE") (pin "3") (pinfunction "A3_3") (pintype "bidirectional"))
      (node (ref "!OE") (pin "3") (pinfunction "A3_3") (pintype "bidirectional"))
      (node (ref "!WE") (pin "3") (pinfunction "A3_3") (pintype "bidirectional"))
      (node (ref "AT28BV25628T") (pin "7") (pinfunction "VCC_7") (pintype "power_in"))
      (node (ref "C10") (pin "1") (pinfunction "1_1") (pintype "passive"))
      (node (ref "C11") (pin "1") (pinfunction "1_1") (pintype "passive"))
      (node (ref "C12") (pin "1") (pinfunction "1_1") (pintype "passive"))
      (node (ref "C13") (pin "1") (pinfunction "1_1") (pintype "passive"))
      (node (ref "C14") (pin "1") (pinfunction "1_1") (pintype "passive"))
      (node (ref "C15") (pin "1") (pinfunction "1_1") (pintype "passive"))
      (node (ref "C16") (pin "1") (pinfunction "1_1") (pintype "passive"))
      (node (ref "C17") (pin "1") (pinfunction "1_1") (pintype "passive"))
      (node (ref "C18") (pin "1") (pinfunction "1_1") (pintype "passive"))
      (node (ref "C19") (pin "1") (pinfunction "1_1") (pintype "passive"))
      (node (ref "C2") (pin "1") (pinfunction "1_1") (pintype "passive"))
      (node (ref "C20") (pin "1") (pinfunction "1_1") (pintype "passive"))
      (node (ref "C21") (pin "1") (pinfunction "1_1") (pintype "passive"))
      (node (ref "C22") (pin "1") (pinfunction "1_1") (pintype "passive"))
      (node (ref "C23") (pin "1") (pinfunction "1_1") (pintype "passive"))
      (node (ref "C24") (pin "1") (pinfunction "1_1") (pintype "passive"))
      (node (ref "C25") (pin "1") (pinfunction "1_1") (pintype "passive"))
      (node (ref "C26") (pin "1") (pinfunction "1_1") (pintype "passive"))
      (node (ref "C27") (pin "1") (pinfunction "1_1") (pintype "passive"))
      (node (ref "C28") (pin "1") (pinfunction "1_1") (pintype "passive"))
      (node (ref "C29") (pin "1") (pinfunction "1_1") (pintype "passive"))
      (node (ref "C3") (pin "1") (pinfunction "1_1") (pintype "passive"))
      (node (ref "C30") (pin "1") (pinfunction "1_1") (pintype "passive"))
      (node (ref "C31") (pin "1") (pinfunction "1_1") (pintype "passive"))
      (node (ref "C32") (pin "1") (pinfunction "1_1") (pintype "passive"))
      (node (ref "C33") (pin "1") (pinfunction "1_1") (pintype "passive"))
      (node (ref "C34") (pin "1") (pinfunction "1_1") (pintype "passive"))
      (node (ref "C35") (pin "1") (pinfunction "1_1") (pintype "passive"))
      (node (ref "C36") (pin "1") (pinfunction "1_1") (pintype "passive"))
      (node (ref "C37") (pin "1") (pinfunction "1_1") (pintype "passive"))
      (node (ref "C38") (pin "1") (pinfunction "1_1") (pintype "passive"))
      (node (ref "C39") (pin "1") (pinfunction "1_1") (pintype "passive"))
      (node (ref "C40") (pin "1") (pinfunction "1_1") (pintype "passive"))
      (node (ref "C41") (pin "1") (pinfunction "1_1") (pintype "passive"))
      (node (ref "C42") (pin "1") (pinfunction "1_1") (pintype "passive"))
      (node (ref "C47") (pin "1") (pinfunction "1_1") (pintype "passive"))
      (node (ref "C51") (pin "1") (pinfunction "1_1") (pintype "passive"))
      (node (ref "C7") (pin "1") (pinfunction "1_1") (pintype "passive"))
      (node (ref "C8") (pin "1") (pinfunction "1_1") (pintype "passive"))
      (node (ref "C9") (pin "1") (pinfunction "1_1") (pintype "passive"))
      (node (ref "COMP_1") (pin "5") (pinfunction "5_5") (pintype "passive"))
      (node (ref "COMP_10") (pin "5") (pinfunction "5_5") (pintype "passive"))
      (node (ref "COMP_11") (pin "5") (pinfunction "5_5") (pintype "passive"))
      (node (ref "COMP_12") (pin "5") (pinfunction "5_5") (pintype "passive"))
      (node (ref "COMP_13") (pin "5") (pinfunction "5_5") (pintype "passive"))
      (node (ref "COMP_14") (pin "5") (pinfunction "5_5") (pintype "passive"))
      (node (ref "COMP_15") (pin "5") (pinfunction "5_5") (pintype "passive"))
      (node (ref "COMP_16") (pin "5") (pinfunction "5_5") (pintype "passive"))
      (node (ref "COMP_17") (pin "5") (pinfunction "5_5") (pintype "passive"))
      (node (ref "COMP_18") (pin "5") (pinfunction "5_5") (pintype "passive"))
      (node (ref "COMP_19") (pin "5") (pinfunction "5_5") (pintype "passive"))
      (node (ref "COMP_2") (pin "5") (pinfunction "5_5") (pintype "passive"))
      (node (ref "COMP_20") (pin "5") (pinfunction "5_5") (pintype "passive"))
      (node (ref "COMP_21") (pin "5") (pinfunction "5_5") (pintype "passive"))
      (node (ref "COMP_22") (pin "5") (pinfunction "5_5") (pintype "passive"))
      (node (ref "COMP_23") (pin "5") (pinfunction "5_5") (pintype "passive"))
      (node (ref "COMP_24") (pin "5") (pinfunction "5_5") (pintype "passive"))
      (node (ref "COMP_25") (pin "5") (pinfunction "5_5") (pintype "passive"))
      (node (ref "COMP_26") (pin "5") (pinfunction "5_5") (pintype "passive"))
      (node (ref "COMP_27") (pin "5") (pinfunction "5_5") (pintype "passive"))
      (node (ref "COMP_28") (pin "5") (pinfunction "5_5") (pintype "passive"))
      (node (ref "COMP_29") (pin "5") (pinfunction "5_5") (pintype "passive"))
      (node (ref "COMP_3") (pin "5") (pinfunction "5_5") (pintype "passive"))
      (node (ref "COMP_30") (pin "5") (pinfunction "5_5") (pintype "passive"))
      (node (ref "COMP_4") (pin "5") (pinfunction "5_5") (pintype "passive"))
      (node (ref "COMP_5") (pin "5") (pinfunction "5_5") (pintype "passive"))
      (node (ref "COMP_6") (pin "5") (pinfunction "5_5") (pintype "passive"))
      (node (ref "COMP_7") (pin "5") (pinfunction "5_5") (pintype "passive"))
      (node (ref "COMP_8") (pin "5") (pinfunction "5_5") (pintype "passive"))
      (node (ref "COMP_9") (pin "5") (pinfunction "5_5") (pintype "passive"))
      (node (ref "IC1") (pin "19") (pinfunction "VCCB_19") (pintype "bidirectional"))
      (node (ref "IO2") (pin "4") (pinfunction "FB_4") (pintype "input"))
      (node (ref "L2") (pin "2") (pinfunction "2_2") (pintype "passive"))
      (node (ref "OR_1") (pin "14") (pinfunction "VCC_14") (pintype "power_in"))
      (node (ref "OR_2") (pin "14") (pinfunction "VCC_14") (pintype "power_in"))
      (node (ref "OR_3") (pin "14") (pinfunction "VCC_14") (pintype "power_in"))
      (node (ref "OR_4") (pin "14") (pinfunction "VCC_14") (pintype "power_in"))
      (node (ref "OR_5") (pin "14") (pinfunction "VCC_14") (pintype "power_in"))
      (node (ref "OR_6") (pin "14") (pinfunction "VCC_14") (pintype "power_in"))
      (node (ref "R77") (pin "1") (pinfunction "1_1") (pintype "passive"))
      (node (ref "TCRT_1") (pin "A") (pinfunction "ANODE_A") (pintype "passive"))
      (node (ref "TCRT_1") (pin "C") (pinfunction "COLLECTOR_C") (pintype "passive"))
      (node (ref "TCRT_10") (pin "A") (pinfunction "ANODE_A") (pintype "passive"))
      (node (ref "TCRT_10") (pin "C") (pinfunction "COLLECTOR_C") (pintype "passive"))
      (node (ref "TCRT_11") (pin "A") (pinfunction "ANODE_A") (pintype "passive"))
      (node (ref "TCRT_11") (pin "C") (pinfunction "COLLECTOR_C") (pintype "passive"))
      (node (ref "TCRT_12") (pin "A") (pinfunction "ANODE_A") (pintype "passive"))
      (node (ref "TCRT_12") (pin "C") (pinfunction "COLLECTOR_C") (pintype "passive"))
      (node (ref "TCRT_13") (pin "A") (pinfunction "ANODE_A") (pintype "passive"))
      (node (ref "TCRT_13") (pin "C") (pinfunction "COLLECTOR_C") (pintype "passive"))
      (node (ref "TCRT_14") (pin "A") (pinfunction "ANODE_A") (pintype "passive"))
      (node (ref "TCRT_14") (pin "C") (pinfunction "COLLECTOR_C") (pintype "passive"))
      (node (ref "TCRT_15") (pin "A") (pinfunction "ANODE_A") (pintype "passive"))
      (node (ref "TCRT_15") (pin "C") (pinfunction "COLLECTOR_C") (pintype "passive"))
      (node (ref "TCRT_16") (pin "A") (pinfunction "ANODE_A") (pintype "passive"))
      (node (ref "TCRT_16") (pin "C") (pinfunction "COLLECTOR_C") (pintype "passive"))
      (node (ref "TCRT_17") (pin "A") (pinfunction "ANODE_A") (pintype "passive"))
      (node (ref "TCRT_17") (pin "C") (pinfunction "COLLECTOR_C") (pintype "passive"))
      (node (ref "TCRT_18") (pin "A") (pinfunction "ANODE_A") (pintype "passive"))
      (node (ref "TCRT_18") (pin "C") (pinfunction "COLLECTOR_C") (pintype "passive"))
      (node (ref "TCRT_19") (pin "A") (pinfunction "ANODE_A") (pintype "passive"))
      (node (ref "TCRT_19") (pin "C") (pinfunction "COLLECTOR_C") (pintype "passive"))
      (node (ref "TCRT_2") (pin "A") (pinfunction "ANODE_A") (pintype "passive"))
      (node (ref "TCRT_2") (pin "C") (pinfunction "COLLECTOR_C") (pintype "passive"))
      (node (ref "TCRT_20") (pin "A") (pinfunction "ANODE_A") (pintype "passive"))
      (node (ref "TCRT_20") (pin "C") (pinfunction "COLLECTOR_C") (pintype "passive"))
      (node (ref "TCRT_21") (pin "A") (pinfunction "ANODE_A") (pintype "passive"))
      (node (ref "TCRT_21") (pin "C") (pinfunction "COLLECTOR_C") (pintype "passive"))
      (node (ref "TCRT_22") (pin "A") (pinfunction "ANODE_A") (pintype "passive"))
      (node (ref "TCRT_22") (pin "C") (pinfunction "COLLECTOR_C") (pintype "passive"))
      (node (ref "TCRT_23") (pin "A") (pinfunction "ANODE_A") (pintype "passive"))
      (node (ref "TCRT_23") (pin "C") (pinfunction "COLLECTOR_C") (pintype "passive"))
      (node (ref "TCRT_24") (pin "A") (pinfunction "ANODE_A") (pintype "passive"))
      (node (ref "TCRT_24") (pin "C") (pinfunction "COLLECTOR_C") (pintype "passive"))
      (node (ref "TCRT_25") (pin "A") (pinfunction "ANODE_A") (pintype "passive"))
      (node (ref "TCRT_25") (pin "C") (pinfunction "COLLECTOR_C") (pintype "passive"))
      (node (ref "TCRT_26") (pin "A") (pinfunction "ANODE_A") (pintype "passive"))
      (node (ref "TCRT_26") (pin "C") (pinfunction "COLLECTOR_C") (pintype "passive"))
      (node (ref "TCRT_27") (pin "A") (pinfunction "ANODE_A") (pintype "passive"))
      (node (ref "TCRT_27") (pin "C") (pinfunction "COLLECTOR_C") (pintype "passive"))
      (node (ref "TCRT_28") (pin "A") (pinfunction "ANODE_A") (pintype "passive"))
      (node (ref "TCRT_28") (pin "C") (pinfunction "COLLECTOR_C") (pintype "passive"))
      (node (ref "TCRT_29") (pin "A") (pinfunction "ANODE_A") (pintype "passive"))
      (node (ref "TCRT_29") (pin "C") (pinfunction "COLLECTOR_C") (pintype "passive"))
      (node (ref "TCRT_3") (pin "A") (pinfunction "ANODE_A") (pintype "passive"))
      (node (ref "TCRT_3") (pin "C") (pinfunction "COLLECTOR_C") (pintype "passive"))
      (node (ref "TCRT_30") (pin "A") (pinfunction "ANODE_A") (pintype "passive"))
      (node (ref "TCRT_30") (pin "C") (pinfunction "COLLECTOR_C") (pintype "passive"))
      (node (ref "TCRT_4") (pin "A") (pinfunction "ANODE_A") (pintype "passive"))
      (node (ref "TCRT_4") (pin "C") (pinfunction "COLLECTOR_C") (pintype "passive"))
      (node (ref "TCRT_5") (pin "A") (pinfunction "ANODE_A") (pintype "passive"))
      (node (ref "TCRT_5") (pin "C") (pinfunction "COLLECTOR_C") (pintype "passive"))
      (node (ref "TCRT_6") (pin "A") (pinfunction "ANODE_A") (pintype "passive"))
      (node (ref "TCRT_6") (pin "C") (pinfunction "COLLECTOR_C") (pintype "passive"))
      (node (ref "TCRT_7") (pin "A") (pinfunction "ANODE_A") (pintype "passive"))
      (node (ref "TCRT_7") (pin "C") (pinfunction "COLLECTOR_C") (pintype "passive"))
      (node (ref "TCRT_8") (pin "A") (pinfunction "ANODE_A") (pintype "passive"))
      (node (ref "TCRT_8") (pin "C") (pinfunction "COLLECTOR_C") (pintype "passive"))
      (node (ref "TCRT_9") (pin "A") (pinfunction "ANODE_A") (pintype "passive"))
      (node (ref "TCRT_9") (pin "C") (pinfunction "COLLECTOR_C") (pintype "passive"))
      (node (ref "TRIM") (pin "3") (pinfunction "3_3") (pintype "passive"))
    )
    (net (code "6") (name "5V_JATSON") (class "Default")
      (node (ref "C4") (pin "1") (pinfunction "1_1") (pintype "passive"))
      (node (ref "C6") (pin "1") (pinfunction "1_1") (pintype "passive"))
      (node (ref "IO1") (pin "4") (pinfunction "FB_4") (pintype "input"))
      (node (ref "L1") (pin "2") (pinfunction "2_2") (pintype "passive"))
      (node (ref "SV1") (pin "22") (pinfunction "22_22") (pintype "passive"))
      (node (ref "SV1") (pin "24") (pinfunction "24_24") (pintype "passive"))
      (node (ref "SV1") (pin "26") (pinfunction "26_26") (pintype "passive"))
    )
    (net (code "7") (name "A0") (class "Default")
      (node (ref "A0") (pin "TP") (pinfunction "TP_TP") (pintype "input"))
      (node (ref "AT28BV25628T") (pin "17") (pinfunction "A0_17") (pintype "passive"))
      (node (ref "R63") (pin "1") (pinfunction "1_1") (pintype "passive"))
    )
    (net (code "8") (name "A1") (class "Default")
      (node (ref "A1") (pin "TP") (pinfunction "TP_TP") (pintype "input"))
      (node (ref "AT28BV25628T") (pin "16") (pinfunction "A1_16") (pintype "passive"))
      (node (ref "R64") (pin "1") (pinfunction "1_1") (pintype "passive"))
    )
    (net (code "9") (name "A2") (class "Default")
      (node (ref "A2") (pin "TP") (pinfunction "TP_TP") (pintype "input"))
      (node (ref "AT28BV25628T") (pin "15") (pinfunction "A2_15") (pintype "passive"))
      (node (ref "R62") (pin "1") (pinfunction "1_1") (pintype "passive"))
    )
    (net (code "10") (name "A3") (class "Default")
      (node (ref "A3") (pin "TP") (pinfunction "TP_TP") (pintype "input"))
      (node (ref "AT28BV25628T") (pin "14") (pinfunction "A3_14") (pintype "passive"))
      (node (ref "R61") (pin "1") (pinfunction "1_1") (pintype "passive"))
    )
    (net (code "11") (name "A4") (class "Default")
      (node (ref "A4") (pin "TP") (pinfunction "TP_TP") (pintype "input"))
      (node (ref "AT28BV25628T") (pin "13") (pinfunction "A4_13") (pintype "passive"))
      (node (ref "R68") (pin "1") (pinfunction "1_1") (pintype "passive"))
    )
    (net (code "12") (name "A5") (class "Default")
      (node (ref "A5") (pin "TP") (pinfunction "TP_TP") (pintype "input"))
      (node (ref "AT28BV25628T") (pin "12") (pinfunction "A5_12") (pintype "passive"))
      (node (ref "R67") (pin "1") (pinfunction "1_1") (pintype "passive"))
    )
    (net (code "13") (name "A6") (class "Default")
      (node (ref "A6") (pin "TP") (pinfunction "TP_TP") (pintype "input"))
      (node (ref "AT28BV25628T") (pin "11") (pinfunction "A6_11") (pintype "passive"))
      (node (ref "R66") (pin "1") (pinfunction "1_1") (pintype "passive"))
    )
    (net (code "14") (name "A7") (class "Default")
      (node (ref "A7") (pin "TP") (pinfunction "TP_TP") (pintype "input"))
      (node (ref "AT28BV25628T") (pin "10") (pinfunction "A7_10") (pintype "passive"))
      (node (ref "R65") (pin "1") (pinfunction "1_1") (pintype "passive"))
    )
    (net (code "15") (name "A8") (class "Default")
      (node (ref "A8") (pin "TP") (pinfunction "TP_TP") (pintype "input"))
      (node (ref "AT28BV25628T") (pin "4") (pinfunction "A8_4") (pintype "passive"))
      (node (ref "R72") (pin "1") (pinfunction "1_1") (pintype "passive"))
    )
    (net (code "16") (name "A9") (class "Default")
      (node (ref "A9") (pin "TP") (pinfunction "TP_TP") (pintype "input"))
      (node (ref "AT28BV25628T") (pin "3") (pinfunction "A9_3") (pintype "passive"))
      (node (ref "R71") (pin "1") (pinfunction "1_1") (pintype "passive"))
    )
    (net (code "17") (name "A10") (class "Default")
      (node (ref "A10") (pin "TP") (pinfunction "TP_TP") (pintype "input"))
      (node (ref "AT28BV25628T") (pin "28") (pinfunction "A10_28") (pintype "passive"))
      (node (ref "R70") (pin "1") (pinfunction "1_1") (pintype "passive"))
    )
    (net (code "18") (name "A11") (class "Default")
      (node (ref "A11") (pin "TP") (pinfunction "TP_TP") (pintype "input"))
      (node (ref "AT28BV25628T") (pin "2") (pinfunction "A11_2") (pintype "passive"))
      (node (ref "R69") (pin "1") (pinfunction "1_1") (pintype "passive"))
    )
    (net (code "19") (name "A12") (class "Default")
      (node (ref "A12") (pin "TP") (pinfunction "TP_TP") (pintype "input"))
      (node (ref "AT28BV25628T") (pin "9") (pinfunction "A12_9") (pintype "passive"))
      (node (ref "R76") (pin "1") (pinfunction "1_1") (pintype "passive"))
    )
    (net (code "20") (name "A13") (class "Default")
      (node (ref "A13") (pin "TP") (pinfunction "TP_TP") (pintype "input"))
      (node (ref "AT28BV25628T") (pin "5") (pinfunction "A13_5") (pintype "passive"))
      (node (ref "R75") (pin "1") (pinfunction "1_1") (pintype "passive"))
    )
    (net (code "21") (name "A14") (class "Default")
      (node (ref "A14") (pin "TP") (pinfunction "TP_TP") (pintype "input"))
      (node (ref "AT28BV25628T") (pin "8") (pinfunction "A14_8") (pintype "passive"))
      (node (ref "R74") (pin "1") (pinfunction "1_1") (pintype "passive"))
    )
    (net (code "22") (name "BAT") (class "Default")
      (node (ref "C1") (pin "1") (pinfunction "1_1") (pintype "passive"))
      (node (ref "C45") (pin "1") (pinfunction "1_1") (pintype "passive"))
      (node (ref "C46") (pin "1") (pinfunction "1_1") (pintype "passive"))
      (node (ref "C5") (pin "1") (pinfunction "1_1") (pintype "passive"))
      (node (ref "IC2") (pin "3") (pinfunction "VIN_3") (pintype "input"))
      (node (ref "IO1") (pin "1") (pinfunction "IN_1") (pintype "input"))
      (node (ref "IO2") (pin "1") (pinfunction "IN_1") (pintype "input"))
      (node (ref "MAIN_POWER") (pin "3") (pinfunction "3-ON_3") (pintype "passive"))
    )
    (net (code "23") (name "BAT_UP") (class "Default")
      (node (ref "FUSE1") (pin "1") (pinfunction "1_1") (pintype "passive"))
      (node (ref "SV1") (pin "11") (pinfunction "11_11") (pintype "passive"))
      (node (ref "SV1") (pin "13") (pinfunction "13_13") (pintype "passive"))
      (node (ref "SV1") (pin "15") (pinfunction "15_15") (pintype "passive"))
      (node (ref "SV1") (pin "17") (pinfunction "17_17") (pintype "passive"))
      (node (ref "SV1") (pin "19") (pinfunction "19_19") (pintype "passive"))
      (node (ref "SV1") (pin "21") (pinfunction "21_21") (pintype "passive"))
      (node (ref "SV1") (pin "23") (pinfunction "23_23") (pintype "passive"))
      (node (ref "SV1") (pin "25") (pinfunction "25_25") (pintype "passive"))
      (node (ref "SV1") (pin "27") (pinfunction "27_27") (pintype "passive"))
      (node (ref "SV1") (pin "9") (pinfunction "9_9") (pintype "passive"))
    )
    (net (code "24") (name "CAPACITOR") (class "Default")
      (node (ref "Q3") (pin "G") (pinfunction "G_G") (pintype "passive"))
      (node (ref "R79") (pin "2") (pinfunction "2_2") (pintype "passive"))
      (node (ref "SV1") (pin "30") (pinfunction "30_30") (pintype "passive"))
    )
    (net (code "25") (name "GND") (class "Default")
      (node (ref "!CE") (pin "1") (pinfunction "A1_1") (pintype "bidirectional"))
      (node (ref "!OE") (pin "1") (pinfunction "A1_1") (pintype "bidirectional"))
      (node (ref "!WE") (pin "1") (pinfunction "A1_1") (pintype "bidirectional"))
      (node (ref "AT28BV25628T") (pin "21") (pinfunction "GND_21") (pintype "power_in"))
      (node (ref "C1") (pin "2") (pinfunction "2_2") (pintype "passive"))
      (node (ref "C10") (pin "2") (pinfunction "2_2") (pintype "passive"))
      (node (ref "C11") (pin "2") (pinfunction "2_2") (pintype "passive"))
      (node (ref "C12") (pin "2") (pinfunction "2_2") (pintype "passive"))
      (node (ref "C13") (pin "2") (pinfunction "2_2") (pintype "passive"))
      (node (ref "C14") (pin "2") (pinfunction "2_2") (pintype "passive"))
      (node (ref "C15") (pin "2") (pinfunction "2_2") (pintype "passive"))
      (node (ref "C16") (pin "2") (pinfunction "2_2") (pintype "passive"))
      (node (ref "C17") (pin "2") (pinfunction "2_2") (pintype "passive"))
      (node (ref "C18") (pin "2") (pinfunction "2_2") (pintype "passive"))
      (node (ref "C19") (pin "2") (pinfunction "2_2") (pintype "passive"))
      (node (ref "C2") (pin "2") (pinfunction "2_2") (pintype "passive"))
      (node (ref "C20") (pin "2") (pinfunction "2_2") (pintype "passive"))
      (node (ref "C21") (pin "2") (pinfunction "2_2") (pintype "passive"))
      (node (ref "C22") (pin "2") (pinfunction "2_2") (pintype "passive"))
      (node (ref "C23") (pin "2") (pinfunction "2_2") (pintype "passive"))
      (node (ref "C24") (pin "2") (pinfunction "2_2") (pintype "passive"))
      (node (ref "C25") (pin "2") (pinfunction "2_2") (pintype "passive"))
      (node (ref "C26") (pin "2") (pinfunction "2_2") (pintype "passive"))
      (node (ref "C27") (pin "2") (pinfunction "2_2") (pintype "passive"))
      (node (ref "C28") (pin "2") (pinfunction "2_2") (pintype "passive"))
      (node (ref "C29") (pin "2") (pinfunction "2_2") (pintype "passive"))
      (node (ref "C3") (pin "2") (pinfunction "2_2") (pintype "passive"))
      (node (ref "C30") (pin "2") (pinfunction "2_2") (pintype "passive"))
      (node (ref "C31") (pin "2") (pinfunction "2_2") (pintype "passive"))
      (node (ref "C32") (pin "2") (pinfunction "2_2") (pintype "passive"))
      (node (ref "C33") (pin "2") (pinfunction "2_2") (pintype "passive"))
      (node (ref "C34") (pin "2") (pinfunction "2_2") (pintype "passive"))
      (node (ref "C35") (pin "2") (pinfunction "2_2") (pintype "passive"))
      (node (ref "C36") (pin "2") (pinfunction "2_2") (pintype "passive"))
      (node (ref "C37") (pin "2") (pinfunction "2_2") (pintype "passive"))
      (node (ref "C38") (pin "2") (pinfunction "2_2") (pintype "passive"))
      (node (ref "C39") (pin "2") (pinfunction "2_2") (pintype "passive"))
      (node (ref "C4") (pin "2") (pinfunction "2_2") (pintype "passive"))
      (node (ref "C40") (pin "2") (pinfunction "2_2") (pintype "passive"))
      (node (ref "C41") (pin "2") (pinfunction "2_2") (pintype "passive"))
      (node (ref "C42") (pin "2") (pinfunction "2_2") (pintype "passive"))
      (node (ref "C43") (pin "2") (pinfunction "2_2") (pintype "passive"))
      (node (ref "C44") (pin "2") (pinfunction "2_2") (pintype "passive"))
      (node (ref "C45") (pin "2") (pinfunction "2_2") (pintype "passive"))
      (node (ref "C46") (pin "2") (pinfunction "2_2") (pintype "passive"))
      (node (ref "C47") (pin "2") (pinfunction "2_2") (pintype "passive"))
      (node (ref "C48") (pin "2") (pinfunction "2_2") (pintype "passive"))
      (node (ref "C49") (pin "-") (pinfunction "-_-") (pintype "passive"))
      (node (ref "C5") (pin "2") (pinfunction "2_2") (pintype "passive"))
      (node (ref "C50") (pin "-") (pinfunction "-_-") (pintype "passive"))
      (node (ref "C51") (pin "2") (pinfunction "2_2") (pintype "passive"))
      (node (ref "C52") (pin "1") (pinfunction "1_1") (pintype "passive"))
      (node (ref "C6") (pin "2") (pinfunction "2_2") (pintype "passive"))
      (node (ref "C7") (pin "2") (pinfunction "2_2") (pintype "passive"))
      (node (ref "C8") (pin "2") (pinfunction "2_2") (pintype "passive"))
      (node (ref "C9") (pin "2") (pinfunction "2_2") (pintype "passive"))
      (node (ref "COMP_1") (pin "2") (pinfunction "2_2") (pintype "passive"))
      (node (ref "COMP_10") (pin "2") (pinfunction "2_2") (pintype "passive"))
      (node (ref "COMP_11") (pin "2") (pinfunction "2_2") (pintype "passive"))
      (node (ref "COMP_12") (pin "2") (pinfunction "2_2") (pintype "passive"))
      (node (ref "COMP_13") (pin "2") (pinfunction "2_2") (pintype "passive"))
      (node (ref "COMP_14") (pin "2") (pinfunction "2_2") (pintype "passive"))
      (node (ref "COMP_15") (pin "2") (pinfunction "2_2") (pintype "passive"))
      (node (ref "COMP_16") (pin "2") (pinfunction "2_2") (pintype "passive"))
      (node (ref "COMP_17") (pin "2") (pinfunction "2_2") (pintype "passive"))
      (node (ref "COMP_18") (pin "2") (pinfunction "2_2") (pintype "passive"))
      (node (ref "COMP_19") (pin "2") (pinfunction "2_2") (pintype "passive"))
      (node (ref "COMP_2") (pin "2") (pinfunction "2_2") (pintype "passive"))
      (node (ref "COMP_20") (pin "2") (pinfunction "2_2") (pintype "passive"))
      (node (ref "COMP_21") (pin "2") (pinfunction "2_2") (pintype "passive"))
      (node (ref "COMP_22") (pin "2") (pinfunction "2_2") (pintype "passive"))
      (node (ref "COMP_23") (pin "2") (pinfunction "2_2") (pintype "passive"))
      (node (ref "COMP_24") (pin "2") (pinfunction "2_2") (pintype "passive"))
      (node (ref "COMP_25") (pin "2") (pinfunction "2_2") (pintype "passive"))
      (node (ref "COMP_26") (pin "2") (pinfunction "2_2") (pintype "passive"))
      (node (ref "COMP_27") (pin "2") (pinfunction "2_2") (pintype "passive"))
      (node (ref "COMP_28") (pin "2") (pinfunction "2_2") (pintype "passive"))
      (node (ref "COMP_29") (pin "2") (pinfunction "2_2") (pintype "passive"))
      (node (ref "COMP_3") (pin "2") (pinfunction "2_2") (pintype "passive"))
      (node (ref "COMP_30") (pin "2") (pinfunction "2_2") (pintype "passive"))
      (node (ref "COMP_4") (pin "2") (pinfunction "2_2") (pintype "passive"))
      (node (ref "COMP_5") (pin "2") (pinfunction "2_2") (pintype "passive"))
      (node (ref "COMP_6") (pin "2") (pinfunction "2_2") (pintype "passive"))
      (node (ref "COMP_7") (pin "2") (pinfunction "2_2") (pintype "passive"))
      (node (ref "COMP_8") (pin "2") (pinfunction "2_2") (pintype "passive"))
      (node (ref "COMP_9") (pin "2") (pinfunction "2_2") (pintype "passive"))
      (node (ref "IC1") (pin "11") (pinfunction "GND_11") (pintype "bidirectional"))
      (node (ref "IC2") (pin "1") (pinfunction "GND_1") (pintype "power_in"))
      (node (ref "IO1") (pin "3") (pinfunction "GND_3") (pintype "power_in"))
      (node (ref "IO1") (pin "5") (pinfunction "EN_5") (pintype "input"))
      (node (ref "IO1") (pin "6") (pinfunction "GND_6") (pintype "power_in"))
      (node (ref "IO2") (pin "3") (pinfunction "GND_3") (pintype "power_in"))
      (node (ref "IO2") (pin "5") (pinfunction "EN_5") (pintype "input"))
      (node (ref "IO2") (pin "6") (pinfunction "GND_6") (pintype "power_in"))
      (node (ref "OR_1") (pin "7") (pinfunction "GND_7") (pintype "power_in"))
      (node (ref "OR_2") (pin "7") (pinfunction "GND_7") (pintype "power_in"))
      (node (ref "OR_3") (pin "7") (pinfunction "GND_7") (pintype "power_in"))
      (node (ref "OR_4") (pin "7") (pinfunction "GND_7") (pintype "power_in"))
      (node (ref "OR_5") (pin "7") (pinfunction "GND_7") (pintype "power_in"))
      (node (ref "OR_6") (pin "7") (pinfunction "GND_7") (pintype "power_in"))
      (node (ref "R1") (pin "2") (pinfunction "2_2") (pintype "passive"))
      (node (ref "R10") (pin "2") (pinfunction "2_2") (pintype "passive"))
      (node (ref "R11") (pin "2") (pinfunction "2_2") (pintype "passive"))
      (node (ref "R12") (pin "2") (pinfunction "2_2") (pintype "passive"))
      (node (ref "R13") (pin "2") (pinfunction "2_2") (pintype "passive"))
      (node (ref "R14") (pin "2") (pinfunction "2_2") (pintype "passive"))
      (node (ref "R15") (pin "2") (pinfunction "2_2") (pintype "passive"))
      (node (ref "R16") (pin "2") (pinfunction "2_2") (pintype "passive"))
      (node (ref "R17") (pin "2") (pinfunction "2_2") (pintype "passive"))
      (node (ref "R18") (pin "2") (pinfunction "2_2") (pintype "passive"))
      (node (ref "R19") (pin "2") (pinfunction "2_2") (pintype "passive"))
      (node (ref "R2") (pin "2") (pinfunction "2_2") (pintype "passive"))
      (node (ref "R20") (pin "2") (pinfunction "2_2") (pintype "passive"))
      (node (ref "R21") (pin "2") (pinfunction "2_2") (pintype "passive"))
      (node (ref "R22") (pin "2") (pinfunction "2_2") (pintype "passive"))
      (node (ref "R23") (pin "2") (pinfunction "2_2") (pintype "passive"))
      (node (ref "R24") (pin "2") (pinfunction "2_2") (pintype "passive"))
      (node (ref "R25") (pin "2") (pinfunction "2_2") (pintype "passive"))
      (node (ref "R26") (pin "2") (pinfunction "2_2") (pintype "passive"))
      (node (ref "R27") (pin "2") (pinfunction "2_2") (pintype "passive"))
      (node (ref "R28") (pin "2") (pinfunction "2_2") (pintype "passive"))
      (node (ref "R29") (pin "2") (pinfunction "2_2") (pintype "passive"))
      (node (ref "R3") (pin "2") (pinfunction "2_2") (pintype "passive"))
      (node (ref "R30") (pin "2") (pinfunction "2_2") (pintype "passive"))
      (node (ref "R31") (pin "2") (pinfunction "2_2") (pintype "passive"))
      (node (ref "R32") (pin "2") (pinfunction "2_2") (pintype "passive"))
      (node (ref "R33") (pin "2") (pinfunction "2_2") (pintype "passive"))
      (node (ref "R34") (pin "2") (pinfunction "2_2") (pintype "passive"))
      (node (ref "R35") (pin "2") (pinfunction "2_2") (pintype "passive"))
      (node (ref "R36") (pin "2") (pinfunction "2_2") (pintype "passive"))
      (node (ref "R37") (pin "2") (pinfunction "2_2") (pintype "passive"))
      (node (ref "R38") (pin "2") (pinfunction "2_2") (pintype "passive"))
      (node (ref "R39") (pin "2") (pinfunction "2_2") (pintype "passive"))
      (node (ref "R4") (pin "2") (pinfunction "2_2") (pintype "passive"))
      (node (ref "R40") (pin "2") (pinfunction "2_2") (pintype "passive"))
      (node (ref "R41") (pin "2") (pinfunction "2_2") (pintype "passive"))
      (node (ref "R42") (pin "2") (pinfunction "2_2") (pintype "passive"))
      (node (ref "R43") (pin "2") (pinfunction "2_2") (pintype "passive"))
      (node (ref "R44") (pin "2") (pinfunction "2_2") (pintype "passive"))
      (node (ref "R45") (pin "2") (pinfunction "2_2") (pintype "passive"))
      (node (ref "R46") (pin "2") (pinfunction "2_2") (pintype "passive"))
      (node (ref "R47") (pin "2") (pinfunction "2_2") (pintype "passive"))
      (node (ref "R48") (pin "2") (pinfunction "2_2") (pintype "passive"))
      (node (ref "R49") (pin "2") (pinfunction "2_2") (pintype "passive"))
      (node (ref "R5") (pin "2") (pinfunction "2_2") (pintype "passive"))
      (node (ref "R50") (pin "2") (pinfunction "2_2") (pintype "passive"))
      (node (ref "R51") (pin "2") (pinfunction "2_2") (pintype "passive"))
      (node (ref "R52") (pin "2") (pinfunction "2_2") (pintype "passive"))
      (node (ref "R53") (pin "2") (pinfunction "2_2") (pintype "passive"))
      (node (ref "R54") (pin "2") (pinfunction "2_2") (pintype "passive"))
      (node (ref "R55") (pin "2") (pinfunction "2_2") (pintype "passive"))
      (node (ref "R56") (pin "2") (pinfunction "2_2") (pintype "passive"))
      (node (ref "R57") (pin "2") (pinfunction "2_2") (pintype "passive"))
      (node (ref "R58") (pin "2") (pinfunction "2_2") (pintype "passive"))
      (node (ref "R59") (pin "2") (pinfunction "2_2") (pintype "passive"))
      (node (ref "R6") (pin "2") (pinfunction "2_2") (pintype "passive"))
      (node (ref "R60") (pin "2") (pinfunction "2_2") (pintype "passive"))
      (node (ref "R7") (pin "2") (pinfunction "2_2") (pintype "passive"))
      (node (ref "R78") (pin "1") (pinfunction "1_1") (pintype "passive"))
      (node (ref "R79") (pin "1") (pinfunction "1_1") (pintype "passive"))
      (node (ref "R8") (pin "2") (pinfunction "2_2") (pintype "passive"))
      (node (ref "R81") (pin "2") (pinfunction "2_2") (pintype "passive"))
      (node (ref "R9") (pin "2") (pinfunction "2_2") (pintype "passive"))
      (node (ref "SOLENOID") (pin "2") (pinfunction "2_2") (pintype "passive"))
      (node (ref "SV1") (pin "1") (pinfunction "1_1") (pintype "passive"))
      (node (ref "SV1") (pin "10") (pinfunction "10_10") (pintype "passive"))
      (node (ref "SV1") (pin "12") (pinfunction "12_12") (pintype "passive"))
      (node (ref "SV1") (pin "14") (pinfunction "14_14") (pintype "passive"))
      (node (ref "SV1") (pin "16") (pinfunction "16_16") (pintype "passive"))
      (node (ref "SV1") (pin "18") (pinfunction "18_18") (pintype "passive"))
      (node (ref "SV1") (pin "2") (pinfunction "2_2") (pintype "passive"))
      (node (ref "SV1") (pin "20") (pinfunction "20_20") (pintype "passive"))
      (node (ref "SV1") (pin "3") (pinfunction "3_3") (pintype "passive"))
      (node (ref "SV1") (pin "4") (pinfunction "4_4") (pintype "passive"))
      (node (ref "SV1") (pin "5") (pinfunction "5_5") (pintype "passive"))
      (node (ref "SV1") (pin "6") (pinfunction "6_6") (pintype "passive"))
      (node (ref "SV1") (pin "7") (pinfunction "7_7") (pintype "passive"))
      (node (ref "SV1") (pin "8") (pinfunction "8_8") (pintype "passive"))
      (node (ref "TRIM") (pin "1") (pinfunction "1_1") (pintype "passive"))
      (node (ref "U$5") (pin "3") (pinfunction "4_3") (pintype "bidirectional"))
      (node (ref "U$5") (pin "4") (pinfunction "3_4") (pintype "bidirectional"))
      (node (ref "Z1") (pin "A") (pinfunction "A_A") (pintype "passive"))
      (node (ref "Z2") (pin "A") (pinfunction "A_A") (pintype "passive"))
    )
    (net (code "26") (name "INT") (class "Default")
      (node (ref "OR_6") (pin "6") (pinfunction "Y2_6") (pintype "output"))
      (node (ref "Q1") (pin "3") (pinfunction "D_3") (pintype "passive"))
      (node (ref "R77") (pin "2") (pinfunction "2_2") (pintype "passive"))
    )
    (net (code "27") (name "INT_3V") (class "Default")
      (node (ref "Q1") (pin "2") (pinfunction "S_2") (pintype "passive"))
      (node (ref "R73") (pin "2") (pinfunction "2_2") (pintype "passive"))
      (node (ref "SV1") (pin "32") (pinfunction "32_32") (pintype "passive"))
    )
    (net (code "28") (name "IO0") (class "Default")
      (node (ref "AT28BV25628T") (pin "18") (pinfunction "I/O0_18") (pintype "bidirectional"))
      (node (ref "IC1") (pin "20") (pinfunction "B1_20") (pintype "bidirectional"))
      (node (ref "IO_0") (pin "TP") (pinfunction "TP_TP") (pintype "input"))
      (node (ref "OR_5") (pin "9") (pinfunction "A3_9") (pintype "input"))
    )
    (net (code "29") (name "IO0,1") (class "Default")
      (node (ref "OR_5") (pin "8") (pinfunction "Y3_8") (pintype "output"))
      (node (ref "OR_6") (pin "10") (pinfunction "B3_10") (pintype "input"))
    )
    (net (code "30") (name "IO0,1,2,3") (class "Default")
      (node (ref "OR_6") (pin "5") (pinfunction "B2_5") (pintype "input"))
      (node (ref "OR_6") (pin "8") (pinfunction "Y3_8") (pintype "output"))
    )
    (net (code "31") (name "IO0_3V") (class "Default")
      (node (ref "IC1") (pin "1") (pinfunction "A1_1") (pintype "bidirectional"))
      (node (ref "SV1") (pin "40") (pinfunction "40_40") (pintype "passive"))
    )
    (net (code "32") (name "IO1") (class "Default")
      (node (ref "AT28BV25628T") (pin "19") (pinfunction "I/O1_19") (pintype "bidirectional"))
      (node (ref "IC1") (pin "18") (pinfunction "B2_18") (pintype "bidirectional"))
      (node (ref "IO_1") (pin "TP") (pinfunction "TP_TP") (pintype "input"))
      (node (ref "OR_5") (pin "10") (pinfunction "B3_10") (pintype "input"))
    )
    (net (code "33") (name "IO1_3V") (class "Default")
      (node (ref "IC1") (pin "3") (pinfunction "A2_3") (pintype "bidirectional"))
      (node (ref "SV1") (pin "39") (pinfunction "39_39") (pintype "passive"))
    )
    (net (code "34") (name "IO2") (class "Default")
      (node (ref "AT28BV25628T") (pin "20") (pinfunction "I/O2_20") (pintype "bidirectional"))
      (node (ref "IC1") (pin "17") (pinfunction "B3_17") (pintype "bidirectional"))
      (node (ref "IO_2") (pin "TP") (pinfunction "TP_TP") (pintype "input"))
      (node (ref "OR_5") (pin "1") (pinfunction "A1_1") (pintype "input"))
    )
    (net (code "35") (name "IO2,3") (class "Default")
      (node (ref "OR_5") (pin "3") (pinfunction "Y1_3") (pintype "output"))
      (node (ref "OR_6") (pin "9") (pinfunction "A3_9") (pintype "input"))
    )
    (net (code "36") (name "IO2_3V") (class "Default")
      (node (ref "IC1") (pin "4") (pinfunction "A3_4") (pintype "bidirectional"))
      (node (ref "SV1") (pin "38") (pinfunction "38_38") (pintype "passive"))
    )
    (net (code "37") (name "IO3") (class "Default")
      (node (ref "AT28BV25628T") (pin "22") (pinfunction "I/O3_22") (pintype "bidirectional"))
      (node (ref "IC1") (pin "16") (pinfunction "B4_16") (pintype "bidirectional"))
      (node (ref "IO_3") (pin "TP") (pinfunction "TP_TP") (pintype "input"))
      (node (ref "OR_5") (pin "2") (pinfunction "B1_2") (pintype "input"))
    )
    (net (code "38") (name "IO3_3V") (class "Default")
      (node (ref "IC1") (pin "5") (pinfunction "A4_5") (pintype "bidirectional"))
      (node (ref "SV1") (pin "37") (pinfunction "37_37") (pintype "passive"))
    )
    (net (code "39") (name "IO4") (class "Default")
      (node (ref "AT28BV25628T") (pin "23") (pinfunction "I/O4_23") (pintype "bidirectional"))
      (node (ref "IC1") (pin "15") (pinfunction "B5_15") (pintype "bidirectional"))
      (node (ref "IO_4") (pin "TP") (pinfunction "TP_TP") (pintype "input"))
      (node (ref "OR_5") (pin "4") (pinfunction "A2_4") (pintype "input"))
    )
    (net (code "40") (name "IO4,5") (class "Default")
      (node (ref "OR_5") (pin "6") (pinfunction "Y2_6") (pintype "output"))
      (node (ref "OR_6") (pin "1") (pinfunction "A1_1") (pintype "input"))
    )
    (net (code "41") (name "IO4,5,6,7") (class "Default")
      (node (ref "OR_6") (pin "3") (pinfunction "Y1_3") (pintype "output"))
      (node (ref "OR_6") (pin "4") (pinfunction "A2_4") (pintype "input"))
    )
    (net (code "42") (name "IO4_3V") (class "Default")
      (node (ref "IC1") (pin "6") (pinfunction "A5_6") (pintype "bidirectional"))
      (node (ref "SV1") (pin "36") (pinfunction "36_36") (pintype "passive"))
    )
    (net (code "43") (name "IO5") (class "Default")
      (node (ref "AT28BV25628T") (pin "24") (pinfunction "I/O5_24") (pintype "bidirectional"))
      (node (ref "IC1") (pin "14") (pinfunction "B6_14") (pintype "bidirectional"))
      (node (ref "IO_5") (pin "TP") (pinfunction "TP_TP") (pintype "input"))
      (node (ref "OR_5") (pin "5") (pinfunction "B2_5") (pintype "input"))
    )
    (net (code "44") (name "IO5_3V") (class "Default")
      (node (ref "IC1") (pin "7") (pinfunction "A6_7") (pintype "bidirectional"))
      (node (ref "SV1") (pin "35") (pinfunction "35_35") (pintype "passive"))
    )
    (net (code "45") (name "IO6") (class "Default")
      (node (ref "AT28BV25628T") (pin "25") (pinfunction "I/O6_25") (pintype "bidirectional"))
      (node (ref "IC1") (pin "13") (pinfunction "B7_13") (pintype "bidirectional"))
      (node (ref "IO_6") (pin "TP") (pinfunction "TP_TP") (pintype "input"))
      (node (ref "OR_5") (pin "12") (pinfunction "A4_12") (pintype "input"))
    )
    (net (code "46") (name "IO6,7") (class "Default")
      (node (ref "OR_5") (pin "11") (pinfunction "Y4_11") (pintype "output"))
      (node (ref "OR_6") (pin "2") (pinfunction "B1_2") (pintype "input"))
    )
    (net (code "47") (name "IO6_3V") (class "Default")
      (node (ref "IC1") (pin "8") (pinfunction "A7_8") (pintype "bidirectional"))
      (node (ref "SV1") (pin "34") (pinfunction "34_34") (pintype "passive"))
    )
    (net (code "48") (name "IO7") (class "Default")
      (node (ref "AT28BV25628T") (pin "26") (pinfunction "I/O7_26") (pintype "bidirectional"))
      (node (ref "IC1") (pin "12") (pinfunction "B8_12") (pintype "bidirectional"))
      (node (ref "IO_7") (pin "TP") (pinfunction "TP_TP") (pintype "input"))
      (node (ref "OR_5") (pin "13") (pinfunction "B4_13") (pintype "input"))
    )
    (net (code "49") (name "IO7_3V") (class "Default")
      (node (ref "IC1") (pin "9") (pinfunction "A8_9") (pintype "bidirectional"))
      (node (ref "SV1") (pin "33") (pinfunction "33_33") (pintype "passive"))
    )
    (net (code "50") (name "KICK") (class "Default")
      (node (ref "Q2") (pin "G") (pinfunction "G_G") (pintype "passive"))
      (node (ref "R78") (pin "2") (pinfunction "2_2") (pintype "passive"))
      (node (ref "SV1") (pin "31") (pinfunction "31_31") (pintype "passive"))
    )
    (net (code "51") (name "L1") (class "Default")
      (node (ref "COMP_1") (pin "4") (pinfunction "4_4") (pintype "passive"))
      (node (ref "OR_1") (pin "1") (pinfunction "A1_1") (pintype "input"))
    )
    (net (code "52") (name "L2") (class "Default")
      (node (ref "COMP_2") (pin "4") (pinfunction "4_4") (pintype "passive"))
      (node (ref "OR_1") (pin "2") (pinfunction "B1_2") (pintype "input"))
    )
    (net (code "53") (name "L3") (class "Default")
      (node (ref "COMP_3") (pin "4") (pinfunction "4_4") (pintype "passive"))
      (node (ref "OR_1") (pin "4") (pinfunction "A2_4") (pintype "input"))
    )
    (net (code "54") (name "L4") (class "Default")
      (node (ref "COMP_4") (pin "4") (pinfunction "4_4") (pintype "passive"))
      (node (ref "OR_1") (pin "5") (pinfunction "B2_5") (pintype "input"))
    )
    (net (code "55") (name "L5") (class "Default")
      (node (ref "COMP_5") (pin "4") (pinfunction "4_4") (pintype "passive"))
      (node (ref "OR_1") (pin "9") (pinfunction "A3_9") (pintype "input"))
    )
    (net (code "56") (name "L6") (class "Default")
      (node (ref "COMP_6") (pin "4") (pinfunction "4_4") (pintype "passive"))
      (node (ref "OR_1") (pin "10") (pinfunction "B3_10") (pintype "input"))
    )
    (net (code "57") (name "L7") (class "Default")
      (node (ref "COMP_7") (pin "4") (pinfunction "4_4") (pintype "passive"))
      (node (ref "OR_1") (pin "12") (pinfunction "A4_12") (pintype "input"))
    )
    (net (code "58") (name "L8") (class "Default")
      (node (ref "COMP_8") (pin "4") (pinfunction "4_4") (pintype "passive"))
      (node (ref "OR_1") (pin "13") (pinfunction "B4_13") (pintype "input"))
    )
    (net (code "59") (name "L9") (class "Default")
      (node (ref "COMP_9") (pin "4") (pinfunction "4_4") (pintype "passive"))
      (node (ref "OR_2") (pin "1") (pinfunction "A1_1") (pintype "input"))
    )
    (net (code "60") (name "L10") (class "Default")
      (node (ref "COMP_10") (pin "4") (pinfunction "4_4") (pintype "passive"))
      (node (ref "OR_2") (pin "2") (pinfunction "B1_2") (pintype "input"))
    )
    (net (code "61") (name "L11") (class "Default")
      (node (ref "COMP_11") (pin "4") (pinfunction "4_4") (pintype "passive"))
      (node (ref "OR_2") (pin "4") (pinfunction "A2_4") (pintype "input"))
    )
    (net (code "62") (name "L12") (class "Default")
      (node (ref "COMP_12") (pin "4") (pinfunction "4_4") (pintype "passive"))
      (node (ref "OR_2") (pin "5") (pinfunction "B2_5") (pintype "input"))
    )
    (net (code "63") (name "L13") (class "Default")
      (node (ref "COMP_13") (pin "4") (pinfunction "4_4") (pintype "passive"))
      (node (ref "OR_2") (pin "9") (pinfunction "A3_9") (pintype "input"))
    )
    (net (code "64") (name "L14") (class "Default")
      (node (ref "COMP_14") (pin "4") (pinfunction "4_4") (pintype "passive"))
      (node (ref "OR_2") (pin "10") (pinfunction "B3_10") (pintype "input"))
    )
    (net (code "65") (name "L15") (class "Default")
      (node (ref "COMP_15") (pin "4") (pinfunction "4_4") (pintype "passive"))
      (node (ref "OR_2") (pin "12") (pinfunction "A4_12") (pintype "input"))
    )
    (net (code "66") (name "L16") (class "Default")
      (node (ref "COMP_16") (pin "4") (pinfunction "4_4") (pintype "passive"))
      (node (ref "OR_2") (pin "13") (pinfunction "B4_13") (pintype "input"))
    )
    (net (code "67") (name "L17") (class "Default")
      (node (ref "COMP_17") (pin "4") (pinfunction "4_4") (pintype "passive"))
      (node (ref "OR_3") (pin "1") (pinfunction "A1_1") (pintype "input"))
    )
    (net (code "68") (name "L18") (class "Default")
      (node (ref "COMP_18") (pin "4") (pinfunction "4_4") (pintype "passive"))
      (node (ref "OR_3") (pin "2") (pinfunction "B1_2") (pintype "input"))
    )
    (net (code "69") (name "L19") (class "Default")
      (node (ref "COMP_19") (pin "4") (pinfunction "4_4") (pintype "passive"))
      (node (ref "OR_3") (pin "4") (pinfunction "A2_4") (pintype "input"))
    )
    (net (code "70") (name "L20") (class "Default")
      (node (ref "COMP_20") (pin "4") (pinfunction "4_4") (pintype "passive"))
      (node (ref "OR_3") (pin "5") (pinfunction "B2_5") (pintype "input"))
    )
    (net (code "71") (name "L21") (class "Default")
      (node (ref "COMP_21") (pin "4") (pinfunction "4_4") (pintype "passive"))
      (node (ref "OR_3") (pin "9") (pinfunction "A3_9") (pintype "input"))
    )
    (net (code "72") (name "L22") (class "Default")
      (node (ref "COMP_22") (pin "4") (pinfunction "4_4") (pintype "passive"))
      (node (ref "OR_3") (pin "10") (pinfunction "B3_10") (pintype "input"))
    )
    (net (code "73") (name "L23") (class "Default")
      (node (ref "COMP_23") (pin "4") (pinfunction "4_4") (pintype "passive"))
      (node (ref "OR_3") (pin "12") (pinfunction "A4_12") (pintype "input"))
    )
    (net (code "74") (name "L24") (class "Default")
      (node (ref "COMP_24") (pin "4") (pinfunction "4_4") (pintype "passive"))
      (node (ref "OR_3") (pin "13") (pinfunction "B4_13") (pintype "input"))
    )
    (net (code "75") (name "L25") (class "Default")
      (node (ref "COMP_25") (pin "4") (pinfunction "4_4") (pintype "passive"))
      (node (ref "OR_4") (pin "1") (pinfunction "A1_1") (pintype "input"))
    )
    (net (code "76") (name "L26") (class "Default")
      (node (ref "COMP_26") (pin "4") (pinfunction "4_4") (pintype "passive"))
      (node (ref "OR_4") (pin "2") (pinfunction "B1_2") (pintype "input"))
    )
    (net (code "77") (name "L27") (class "Default")
      (node (ref "COMP_27") (pin "4") (pinfunction "4_4") (pintype "passive"))
      (node (ref "OR_4") (pin "4") (pinfunction "A2_4") (pintype "input"))
    )
    (net (code "78") (name "L28") (class "Default")
      (node (ref "COMP_28") (pin "4") (pinfunction "4_4") (pintype "passive"))
      (node (ref "OR_4") (pin "5") (pinfunction "B2_5") (pintype "input"))
    )
    (net (code "79") (name "L29") (class "Default")
      (node (ref "COMP_29") (pin "4") (pinfunction "4_4") (pintype "passive"))
      (node (ref "OR_4") (pin "9") (pinfunction "A3_9") (pintype "input"))
    )
    (net (code "80") (name "L30") (class "Default")
      (node (ref "COMP_30") (pin "4") (pinfunction "4_4") (pintype "passive"))
      (node (ref "OR_4") (pin "10") (pinfunction "B3_10") (pintype "input"))
    )
    (net (code "81") (name "Net-(C49-Pad+)") (class "Default")
      (node (ref "C49") (pin "+") (pinfunction "+_+") (pintype "passive"))
      (node (ref "C50") (pin "+") (pinfunction "+_+") (pintype "passive"))
      (node (ref "Q2") (pin "D") (pinfunction "D_D") (pintype "passive"))
      (node (ref "Q3") (pin "S") (pinfunction "S_S") (pintype "passive"))
      (node (ref "R80") (pin "1") (pinfunction "1_1") (pintype "passive"))
    )
    (net (code "82") (name "Net-(FUSE-Pad2)") (class "Default")
      (node (ref "FUSE") (pin "2") (pinfunction "2_2") (pintype "passive"))
      (node (ref "FUSE1") (pin "2") (pinfunction "2_2") (pintype "passive"))
      (node (ref "FUSE2") (pin "2") (pinfunction "2_2") (pintype "passive"))
      (node (ref "U$4") (pin "1") (pinfunction "1_1") (pintype "bidirectional"))
      (node (ref "U$4") (pin "2") (pinfunction "2_2") (pintype "bidirectional"))
    )
    (net (code "83") (name "Net-(IO1-OUT)") (class "Default")
      (node (ref "IO1") (pin "2") (pinfunction "OUT_2") (pintype "output"))
      (node (ref "L1") (pin "1") (pinfunction "1_1") (pintype "passive"))
      (node (ref "Z2") (pin "C") (pinfunction "C_C") (pintype "passive"))
    )
    (net (code "84") (name "Net-(IO2-OUT)") (class "Default")
      (node (ref "IO2") (pin "2") (pinfunction "OUT_2") (pintype "output"))
      (node (ref "L2") (pin "1") (pinfunction "1_1") (pintype "passive"))
      (node (ref "Z1") (pin "C") (pinfunction "C_C") (pintype "passive"))
    )
    (net (code "85") (name "Net-(MAIN_POWER-2-COM)") (class "Default")
      (node (ref "FUSE") (pin "1") (pinfunction "1_1") (pintype "passive"))
      (node (ref "MAIN_POWER") (pin "2") (pinfunction "2-COM_2") (pintype "passive"))
    )
    (net (code "86") (name "Net-(Q2-PadS)") (class "Default")
      (node (ref "Q2") (pin "S") (pinfunction "S_S") (pintype "passive"))
      (node (ref "SOLENOID") (pin "1") (pinfunction "1_1") (pintype "passive"))
    )
    (net (code "87") (name "Net-(TCRT_1-CATHODE)") (class "Default")
      (node (ref "R1") (pin "1") (pinfunction "1_1") (pintype "passive"))
      (node (ref "TCRT_1") (pin "K") (pinfunction "CATHODE_K") (pintype "passive"))
    )
    (net (code "88") (name "Net-(TCRT_1-EMITTER)") (class "Default")
      (node (ref "1") (pin "TP") (pinfunction "TP_TP") (pintype "input"))
      (node (ref "COMP_1") (pin "3") (pinfunction "3_3") (pintype "passive"))
      (node (ref "R2") (pin "1") (pinfunction "1_1") (pintype "passive"))
      (node (ref "TCRT_1") (pin "E") (pinfunction "EMITTER_E") (pintype "passive"))
    )
    (net (code "89") (name "Net-(TCRT_2-CATHODE)") (class "Default")
      (node (ref "R3") (pin "1") (pinfunction "1_1") (pintype "passive"))
      (node (ref "TCRT_2") (pin "K") (pinfunction "CATHODE_K") (pintype "passive"))
    )
    (net (code "90") (name "Net-(TCRT_2-EMITTER)") (class "Default")
      (node (ref "2") (pin "TP") (pinfunction "TP_TP") (pintype "input"))
      (node (ref "COMP_2") (pin "3") (pinfunction "3_3") (pintype "passive"))
      (node (ref "R4") (pin "1") (pinfunction "1_1") (pintype "passive"))
      (node (ref "TCRT_2") (pin "E") (pinfunction "EMITTER_E") (pintype "passive"))
    )
    (net (code "91") (name "Net-(TCRT_3-CATHODE)") (class "Default")
      (node (ref "R5") (pin "1") (pinfunction "1_1") (pintype "passive"))
      (node (ref "TCRT_3") (pin "K") (pinfunction "CATHODE_K") (pintype "passive"))
    )
    (net (code "92") (name "Net-(TCRT_3-EMITTER)") (class "Default")
      (node (ref "3") (pin "TP") (pinfunction "TP_TP") (pintype "input"))
      (node (ref "COMP_3") (pin "3") (pinfunction "3_3") (pintype "passive"))
      (node (ref "R6") (pin "1") (pinfunction "1_1") (pintype "passive"))
      (node (ref "TCRT_3") (pin "E") (pinfunction "EMITTER_E") (pintype "passive"))
    )
    (net (code "93") (name "Net-(TCRT_4-CATHODE)") (class "Default")
      (node (ref "R7") (pin "1") (pinfunction "1_1") (pintype "passive"))
      (node (ref "TCRT_4") (pin "K") (pinfunction "CATHODE_K") (pintype "passive"))
    )
    (net (code "94") (name "Net-(TCRT_4-EMITTER)") (class "Default")
      (node (ref "4") (pin "TP") (pinfunction "TP_TP") (pintype "input"))
      (node (ref "COMP_4") (pin "3") (pinfunction "3_3") (pintype "passive"))
      (node (ref "R8") (pin "1") (pinfunction "1_1") (pintype "passive"))
      (node (ref "TCRT_4") (pin "E") (pinfunction "EMITTER_E") (pintype "passive"))
    )
    (net (code "95") (name "Net-(TCRT_5-CATHODE)") (class "Default")
      (node (ref "R9") (pin "1") (pinfunction "1_1") (pintype "passive"))
      (node (ref "TCRT_5") (pin "K") (pinfunction "CATHODE_K") (pintype "passive"))
    )
    (net (code "96") (name "Net-(TCRT_5-EMITTER)") (class "Default")
      (node (ref "5") (pin "TP") (pinfunction "TP_TP") (pintype "input"))
      (node (ref "COMP_5") (pin "3") (pinfunction "3_3") (pintype "passive"))
      (node (ref "R10") (pin "1") (pinfunction "1_1") (pintype "passive"))
      (node (ref "TCRT_5") (pin "E") (pinfunction "EMITTER_E") (pintype "passive"))
    )
    (net (code "97") (name "Net-(TCRT_6-CATHODE)") (class "Default")
      (node (ref "R11") (pin "1") (pinfunction "1_1") (pintype "passive"))
      (node (ref "TCRT_6") (pin "K") (pinfunction "CATHODE_K") (pintype "passive"))
    )
    (net (code "98") (name "Net-(TCRT_6-EMITTER)") (class "Default")
      (node (ref "6") (pin "TP") (pinfunction "TP_TP") (pintype "input"))
      (node (ref "COMP_6") (pin "3") (pinfunction "3_3") (pintype "passive"))
      (node (ref "R12") (pin "1") (pinfunction "1_1") (pintype "passive"))
      (node (ref "TCRT_6") (pin "E") (pinfunction "EMITTER_E") (pintype "passive"))
    )
    (net (code "99") (name "Net-(TCRT_7-CATHODE)") (class "Default")
      (node (ref "R13") (pin "1") (pinfunction "1_1") (pintype "passive"))
      (node (ref "TCRT_7") (pin "K") (pinfunction "CATHODE_K") (pintype "passive"))
    )
    (net (code "100") (name "Net-(TCRT_7-EMITTER)") (class "Default")
      (node (ref "7") (pin "TP") (pinfunction "TP_TP") (pintype "input"))
      (node (ref "COMP_7") (pin "3") (pinfunction "3_3") (pintype "passive"))
      (node (ref "R14") (pin "1") (pinfunction "1_1") (pintype "passive"))
      (node (ref "TCRT_7") (pin "E") (pinfunction "EMITTER_E") (pintype "passive"))
    )
    (net (code "101") (name "Net-(TCRT_8-CATHODE)") (class "Default")
      (node (ref "R15") (pin "1") (pinfunction "1_1") (pintype "passive"))
      (node (ref "TCRT_8") (pin "K") (pinfunction "CATHODE_K") (pintype "passive"))
    )
    (net (code "102") (name "Net-(TCRT_8-EMITTER)") (class "Default")
      (node (ref "8") (pin "TP") (pinfunction "TP_TP") (pintype "input"))
      (node (ref "COMP_8") (pin "3") (pinfunction "3_3") (pintype "passive"))
      (node (ref "R16") (pin "1") (pinfunction "1_1") (pintype "passive"))
      (node (ref "TCRT_8") (pin "E") (pinfunction "EMITTER_E") (pintype "passive"))
    )
    (net (code "103") (name "Net-(TCRT_9-CATHODE)") (class "Default")
      (node (ref "R17") (pin "1") (pinfunction "1_1") (pintype "passive"))
      (node (ref "TCRT_9") (pin "K") (pinfunction "CATHODE_K") (pintype "passive"))
    )
    (net (code "104") (name "Net-(TCRT_9-EMITTER)") (class "Default")
      (node (ref "9") (pin "TP") (pinfunction "TP_TP") (pintype "input"))
      (node (ref "COMP_9") (pin "3") (pinfunction "3_3") (pintype "passive"))
      (node (ref "R18") (pin "1") (pinfunction "1_1") (pintype "passive"))
      (node (ref "TCRT_9") (pin "E") (pinfunction "EMITTER_E") (pintype "passive"))
    )
    (net (code "105") (name "Net-(TCRT_10-CATHODE)") (class "Default")
      (node (ref "R19") (pin "1") (pinfunction "1_1") (pintype "passive"))
      (node (ref "TCRT_10") (pin "K") (pinfunction "CATHODE_K") (pintype "passive"))
    )
    (net (code "106") (name "Net-(TCRT_10-EMITTER)") (class "Default")
      (node (ref "10") (pin "TP") (pinfunction "TP_TP") (pintype "input"))
      (node (ref "COMP_10") (pin "3") (pinfunction "3_3") (pintype "passive"))
      (node (ref "R20") (pin "1") (pinfunction "1_1") (pintype "passive"))
      (node (ref "TCRT_10") (pin "E") (pinfunction "EMITTER_E") (pintype "passive"))
    )
    (net (code "107") (name "Net-(TCRT_11-CATHODE)") (class "Default")
      (node (ref "R21") (pin "1") (pinfunction "1_1") (pintype "passive"))
      (node (ref "TCRT_11") (pin "K") (pinfunction "CATHODE_K") (pintype "passive"))
    )
    (net (code "108") (name "Net-(TCRT_11-EMITTER)") (class "Default")
      (node (ref "11") (pin "TP") (pinfunction "TP_TP") (pintype "input"))
      (node (ref "COMP_11") (pin "3") (pinfunction "3_3") (pintype "passive"))
      (node (ref "R22") (pin "1") (pinfunction "1_1") (pintype "passive"))
      (node (ref "TCRT_11") (pin "E") (pinfunction "EMITTER_E") (pintype "passive"))
    )
    (net (code "109") (name "Net-(TCRT_12-CATHODE)") (class "Default")
      (node (ref "R23") (pin "1") (pinfunction "1_1") (pintype "passive"))
      (node (ref "TCRT_12") (pin "K") (pinfunction "CATHODE_K") (pintype "passive"))
    )
    (net (code "110") (name "Net-(TCRT_12-EMITTER)") (class "Default")
      (node (ref "12") (pin "TP") (pinfunction "TP_TP") (pintype "input"))
      (node (ref "COMP_12") (pin "3") (pinfunction "3_3") (pintype "passive"))
      (node (ref "R24") (pin "1") (pinfunction "1_1") (pintype "passive"))
      (node (ref "TCRT_12") (pin "E") (pinfunction "EMITTER_E") (pintype "passive"))
    )
    (net (code "111") (name "Net-(TCRT_13-CATHODE)") (class "Default")
      (node (ref "R25") (pin "1") (pinfunction "1_1") (pintype "passive"))
      (node (ref "TCRT_13") (pin "K") (pinfunction "CATHODE_K") (pintype "passive"))
    )
    (net (code "112") (name "Net-(TCRT_13-EMITTER)") (class "Default")
      (node (ref "13") (pin "TP") (pinfunction "TP_TP") (pintype "input"))
      (node (ref "COMP_13") (pin "3") (pinfunction "3_3") (pintype "passive"))
      (node (ref "R26") (pin "1") (pinfunction "1_1") (pintype "passive"))
      (node (ref "TCRT_13") (pin "E") (pinfunction "EMITTER_E") (pintype "passive"))
    )
    (net (code "113") (name "Net-(TCRT_14-CATHODE)") (class "Default")
      (node (ref "R27") (pin "1") (pinfunction "1_1") (pintype "passive"))
      (node (ref "TCRT_14") (pin "K") (pinfunction "CATHODE_K") (pintype "passive"))
    )
    (net (code "114") (name "Net-(TCRT_14-EMITTER)") (class "Default")
      (node (ref "14") (pin "TP") (pinfunction "TP_TP") (pintype "input"))
      (node (ref "COMP_14") (pin "3") (pinfunction "3_3") (pintype "passive"))
      (node (ref "R28") (pin "1") (pinfunction "1_1") (pintype "passive"))
      (node (ref "TCRT_14") (pin "E") (pinfunction "EMITTER_E") (pintype "passive"))
    )
    (net (code "115") (name "Net-(TCRT_15-CATHODE)") (class "Default")
      (node (ref "R29") (pin "1") (pinfunction "1_1") (pintype "passive"))
      (node (ref "TCRT_15") (pin "K") (pinfunction "CATHODE_K") (pintype "passive"))
    )
    (net (code "116") (name "Net-(TCRT_15-EMITTER)") (class "Default")
      (node (ref "15") (pin "TP") (pinfunction "TP_TP") (pintype "input"))
      (node (ref "COMP_15") (pin "3") (pinfunction "3_3") (pintype "passive"))
      (node (ref "R30") (pin "1") (pinfunction "1_1") (pintype "passive"))
      (node (ref "TCRT_15") (pin "E") (pinfunction "EMITTER_E") (pintype "passive"))
    )
    (net (code "117") (name "Net-(TCRT_16-CATHODE)") (class "Default")
      (node (ref "R31") (pin "1") (pinfunction "1_1") (pintype "passive"))
      (node (ref "TCRT_16") (pin "K") (pinfunction "CATHODE_K") (pintype "passive"))
    )
    (net (code "118") (name "Net-(TCRT_16-EMITTER)") (class "Default")
      (node (ref "16") (pin "TP") (pinfunction "TP_TP") (pintype "input"))
      (node (ref "COMP_16") (pin "3") (pinfunction "3_3") (pintype "passive"))
      (node (ref "R32") (pin "1") (pinfunction "1_1") (pintype "passive"))
      (node (ref "TCRT_16") (pin "E") (pinfunction "EMITTER_E") (pintype "passive"))
    )
    (net (code "119") (name "Net-(TCRT_17-CATHODE)") (class "Default")
      (node (ref "R33") (pin "1") (pinfunction "1_1") (pintype "passive"))
      (node (ref "TCRT_17") (pin "K") (pinfunction "CATHODE_K") (pintype "passive"))
    )
    (net (code "120") (name "Net-(TCRT_17-EMITTER)") (class "Default")
      (node (ref "17") (pin "TP") (pinfunction "TP_TP") (pintype "input"))
      (node (ref "COMP_17") (pin "3") (pinfunction "3_3") (pintype "passive"))
      (node (ref "R34") (pin "1") (pinfunction "1_1") (pintype "passive"))
      (node (ref "TCRT_17") (pin "E") (pinfunction "EMITTER_E") (pintype "passive"))
    )
    (net (code "121") (name "Net-(TCRT_18-CATHODE)") (class "Default")
      (node (ref "R35") (pin "1") (pinfunction "1_1") (pintype "passive"))
      (node (ref "TCRT_18") (pin "K") (pinfunction "CATHODE_K") (pintype "passive"))
    )
    (net (code "122") (name "Net-(TCRT_18-EMITTER)") (class "Default")
      (node (ref "18") (pin "TP") (pinfunction "TP_TP") (pintype "input"))
      (node (ref "COMP_18") (pin "3") (pinfunction "3_3") (pintype "passive"))
      (node (ref "R36") (pin "1") (pinfunction "1_1") (pintype "passive"))
      (node (ref "TCRT_18") (pin "E") (pinfunction "EMITTER_E") (pintype "passive"))
    )
    (net (code "123") (name "Net-(TCRT_19-CATHODE)") (class "Default")
      (node (ref "R37") (pin "1") (pinfunction "1_1") (pintype "passive"))
      (node (ref "TCRT_19") (pin "K") (pinfunction "CATHODE_K") (pintype "passive"))
    )
    (net (code "124") (name "Net-(TCRT_19-EMITTER)") (class "Default")
      (node (ref "19") (pin "TP") (pinfunction "TP_TP") (pintype "input"))
      (node (ref "COMP_19") (pin "3") (pinfunction "3_3") (pintype "passive"))
      (node (ref "R38") (pin "1") (pinfunction "1_1") (pintype "passive"))
      (node (ref "TCRT_19") (pin "E") (pinfunction "EMITTER_E") (pintype "passive"))
    )
    (net (code "125") (name "Net-(TCRT_20-CATHODE)") (class "Default")
      (node (ref "R39") (pin "1") (pinfunction "1_1") (pintype "passive"))
      (node (ref "TCRT_20") (pin "K") (pinfunction "CATHODE_K") (pintype "passive"))
    )
    (net (code "126") (name "Net-(TCRT_20-EMITTER)") (class "Default")
      (node (ref "20") (pin "TP") (pinfunction "TP_TP") (pintype "input"))
      (node (ref "COMP_20") (pin "3") (pinfunction "3_3") (pintype "passive"))
      (node (ref "R40") (pin "1") (pinfunction "1_1") (pintype "passive"))
      (node (ref "TCRT_20") (pin "E") (pinfunction "EMITTER_E") (pintype "passive"))
    )
    (net (code "127") (name "Net-(TCRT_21-CATHODE)") (class "Default")
      (node (ref "R41") (pin "1") (pinfunction "1_1") (pintype "passive"))
      (node (ref "TCRT_21") (pin "K") (pinfunction "CATHODE_K") (pintype "passive"))
    )
    (net (code "128") (name "Net-(TCRT_21-EMITTER)") (class "Default")
      (node (ref "21") (pin "TP") (pinfunction "TP_TP") (pintype "input"))
      (node (ref "COMP_21") (pin "3") (pinfunction "3_3") (pintype "passive"))
      (node (ref "R42") (pin "1") (pinfunction "1_1") (pintype "passive"))
      (node (ref "TCRT_21") (pin "E") (pinfunction "EMITTER_E") (pintype "passive"))
    )
    (net (code "129") (name "Net-(TCRT_22-CATHODE)") (class "Default")
      (node (ref "R43") (pin "1") (pinfunction "1_1") (pintype "passive"))
      (node (ref "TCRT_22") (pin "K") (pinfunction "CATHODE_K") (pintype "passive"))
    )
    (net (code "130") (name "Net-(TCRT_22-EMITTER)") (class "Default")
      (node (ref "22") (pin "TP") (pinfunction "TP_TP") (pintype "input"))
      (node (ref "COMP_22") (pin "3") (pinfunction "3_3") (pintype "passive"))
      (node (ref "R44") (pin "1") (pinfunction "1_1") (pintype "passive"))
      (node (ref "TCRT_22") (pin "E") (pinfunction "EMITTER_E") (pintype "passive"))
    )
    (net (code "131") (name "Net-(TCRT_23-CATHODE)") (class "Default")
      (node (ref "R45") (pin "1") (pinfunction "1_1") (pintype "passive"))
      (node (ref "TCRT_23") (pin "K") (pinfunction "CATHODE_K") (pintype "passive"))
    )
    (net (code "132") (name "Net-(TCRT_23-EMITTER)") (class "Default")
      (node (ref "23") (pin "TP") (pinfunction "TP_TP") (pintype "input"))
      (node (ref "COMP_23") (pin "3") (pinfunction "3_3") (pintype "passive"))
      (node (ref "R46") (pin "1") (pinfunction "1_1") (pintype "passive"))
      (node (ref "TCRT_23") (pin "E") (pinfunction "EMITTER_E") (pintype "passive"))
    )
    (net (code "133") (name "Net-(TCRT_24-CATHODE)") (class "Default")
      (node (ref "R47") (pin "1") (pinfunction "1_1") (pintype "passive"))
      (node (ref "TCRT_24") (pin "K") (pinfunction "CATHODE_K") (pintype "passive"))
    )
    (net (code "134") (name "Net-(TCRT_24-EMITTER)") (class "Default")
      (node (ref "24") (pin "TP") (pinfunction "TP_TP") (pintype "input"))
      (node (ref "COMP_24") (pin "3") (pinfunction "3_3") (pintype "passive"))
      (node (ref "R48") (pin "1") (pinfunction "1_1") (pintype "passive"))
      (node (ref "TCRT_24") (pin "E") (pinfunction "EMITTER_E") (pintype "passive"))
    )
    (net (code "135") (name "Net-(TCRT_25-CATHODE)") (class "Default")
      (node (ref "R49") (pin "1") (pinfunction "1_1") (pintype "passive"))
      (node (ref "TCRT_25") (pin "K") (pinfunction "CATHODE_K") (pintype "passive"))
    )
    (net (code "136") (name "Net-(TCRT_25-EMITTER)") (class "Default")
      (node (ref "25") (pin "TP") (pinfunction "TP_TP") (pintype "input"))
      (node (ref "COMP_25") (pin "3") (pinfunction "3_3") (pintype "passive"))
      (node (ref "R50") (pin "1") (pinfunction "1_1") (pintype "passive"))
      (node (ref "TCRT_25") (pin "E") (pinfunction "EMITTER_E") (pintype "passive"))
    )
    (net (code "137") (name "Net-(TCRT_26-CATHODE)") (class "Default")
      (node (ref "R51") (pin "1") (pinfunction "1_1") (pintype "passive"))
      (node (ref "TCRT_26") (pin "K") (pinfunction "CATHODE_K") (pintype "passive"))
    )
    (net (code "138") (name "Net-(TCRT_26-EMITTER)") (class "Default")
      (node (ref "26") (pin "TP") (pinfunction "TP_TP") (pintype "input"))
      (node (ref "COMP_26") (pin "3") (pinfunction "3_3") (pintype "passive"))
      (node (ref "R52") (pin "1") (pinfunction "1_1") (pintype "passive"))
      (node (ref "TCRT_26") (pin "E") (pinfunction "EMITTER_E") (pintype "passive"))
    )
    (net (code "139") (name "Net-(TCRT_27-CATHODE)") (class "Default")
      (node (ref "R53") (pin "1") (pinfunction "1_1") (pintype "passive"))
      (node (ref "TCRT_27") (pin "K") (pinfunction "CATHODE_K") (pintype "passive"))
    )
    (net (code "140") (name "Net-(TCRT_27-EMITTER)") (class "Default")
      (node (ref "27") (pin "TP") (pinfunction "TP_TP") (pintype "input"))
      (node (ref "COMP_27") (pin "3") (pinfunction "3_3") (pintype "passive"))
      (node (ref "R54") (pin "1") (pinfunction "1_1") (pintype "passive"))
      (node (ref "TCRT_27") (pin "E") (pinfunction "EMITTER_E") (pintype "passive"))
    )
    (net (code "141") (name "Net-(TCRT_28-CATHODE)") (class "Default")
      (node (ref "R55") (pin "1") (pinfunction "1_1") (pintype "passive"))
      (node (ref "TCRT_28") (pin "K") (pinfunction "CATHODE_K") (pintype "passive"))
    )
    (net (code "142") (name "Net-(TCRT_28-EMITTER)") (class "Default")
      (node (ref "28") (pin "TP") (pinfunction "TP_TP") (pintype "input"))
      (node (ref "COMP_28") (pin "3") (pinfunction "3_3") (pintype "passive"))
      (node (ref "R56") (pin "1") (pinfunction "1_1") (pintype "passive"))
      (node (ref "TCRT_28") (pin "E") (pinfunction "EMITTER_E") (pintype "passive"))
    )
    (net (code "143") (name "Net-(TCRT_29-CATHODE)") (class "Default")
      (node (ref "R57") (pin "1") (pinfunction "1_1") (pintype "passive"))
      (node (ref "TCRT_29") (pin "K") (pinfunction "CATHODE_K") (pintype "passive"))
    )
    (net (code "144") (name "Net-(TCRT_29-EMITTER)") (class "Default")
      (node (ref "29") (pin "TP") (pinfunction "TP_TP") (pintype "input"))
      (node (ref "COMP_29") (pin "3") (pinfunction "3_3") (pintype "passive"))
      (node (ref "R58") (pin "1") (pinfunction "1_1") (pintype "passive"))
      (node (ref "TCRT_29") (pin "E") (pinfunction "EMITTER_E") (pintype "passive"))
    )
    (net (code "145") (name "Net-(TCRT_30-CATHODE)") (class "Default")
      (node (ref "R59") (pin "1") (pinfunction "1_1") (pintype "passive"))
      (node (ref "TCRT_30") (pin "K") (pinfunction "CATHODE_K") (pintype "passive"))
    )
    (net (code "146") (name "Net-(TCRT_30-EMITTER)") (class "Default")
      (node (ref "30") (pin "TP") (pinfunction "TP_TP") (pintype "input"))
      (node (ref "COMP_30") (pin "3") (pinfunction "3_3") (pintype "passive"))
      (node (ref "R60") (pin "1") (pinfunction "1_1") (pintype "passive"))
      (node (ref "TCRT_30") (pin "E") (pinfunction "EMITTER_E") (pintype "passive"))
    )
    (net (code "147") (name "Net-(U$4-3)") (class "Default")
      (node (ref "U$4") (pin "3") (pinfunction "4_3") (pintype "bidirectional"))
      (node (ref "U$4") (pin "4") (pinfunction "3_4") (pintype "bidirectional"))
      (node (ref "U$5") (pin "1") (pinfunction "1_1") (pintype "bidirectional"))
      (node (ref "U$5") (pin "2") (pinfunction "2_2") (pintype "bidirectional"))
    )
    (net (code "148") (name "REF") (class "Default")
      (node (ref "C52") (pin "2") (pinfunction "2_2") (pintype "passive"))
      (node (ref "COMP_1") (pin "1") (pinfunction "1_1") (pintype "passive"))
      (node (ref "COMP_10") (pin "1") (pinfunction "1_1") (pintype "passive"))
      (node (ref "COMP_11") (pin "1") (pinfunction "1_1") (pintype "passive"))
      (node (ref "COMP_12") (pin "1") (pinfunction "1_1") (pintype "passive"))
      (node (ref "COMP_13") (pin "1") (pinfunction "1_1") (pintype "passive"))
      (node (ref "COMP_14") (pin "1") (pinfunction "1_1") (pintype "passive"))
      (node (ref "COMP_15") (pin "1") (pinfunction "1_1") (pintype "passive"))
      (node (ref "COMP_16") (pin "1") (pinfunction "1_1") (pintype "passive"))
      (node (ref "COMP_17") (pin "1") (pinfunction "1_1") (pintype "passive"))
      (node (ref "COMP_18") (pin "1") (pinfunction "1_1") (pintype "passive"))
      (node (ref "COMP_19") (pin "1") (pinfunction "1_1") (pintype "passive"))
      (node (ref "COMP_2") (pin "1") (pinfunction "1_1") (pintype "passive"))
      (node (ref "COMP_20") (pin "1") (pinfunction "1_1") (pintype "passive"))
      (node (ref "COMP_21") (pin "1") (pinfunction "1_1") (pintype "passive"))
      (node (ref "COMP_22") (pin "1") (pinfunction "1_1") (pintype "passive"))
      (node (ref "COMP_23") (pin "1") (pinfunction "1_1") (pintype "passive"))
      (node (ref "COMP_24") (pin "1") (pinfunction "1_1") (pintype "passive"))
      (node (ref "COMP_25") (pin "1") (pinfunction "1_1") (pintype "passive"))
      (node (ref "COMP_26") (pin "1") (pinfunction "1_1") (pintype "passive"))
      (node (ref "COMP_27") (pin "1") (pinfunction "1_1") (pintype "passive"))
      (node (ref "COMP_28") (pin "1") (pinfunction "1_1") (pintype "passive"))
      (node (ref "COMP_29") (pin "1") (pinfunction "1_1") (pintype "passive"))
      (node (ref "COMP_3") (pin "1") (pinfunction "1_1") (pintype "passive"))
      (node (ref "COMP_30") (pin "1") (pinfunction "1_1") (pintype "passive"))
      (node (ref "COMP_4") (pin "1") (pinfunction "1_1") (pintype "passive"))
      (node (ref "COMP_5") (pin "1") (pinfunction "1_1") (pintype "passive"))
      (node (ref "COMP_6") (pin "1") (pinfunction "1_1") (pintype "passive"))
      (node (ref "COMP_7") (pin "1") (pinfunction "1_1") (pintype "passive"))
      (node (ref "COMP_8") (pin "1") (pinfunction "1_1") (pintype "passive"))
      (node (ref "COMP_9") (pin "1") (pinfunction "1_1") (pintype "passive"))
      (node (ref "TRIM") (pin "2") (pinfunction "2_2") (pintype "passive"))
    )
    (net (code "149") (name "SOLENOID") (class "Default")
      (node (ref "FUSE2") (pin "1") (pinfunction "1_1") (pintype "passive"))
      (node (ref "Q3") (pin "D") (pinfunction "D_D") (pintype "passive"))
    )
    (net (code "150") (name "V_CAP") (class "Default")
      (node (ref "R80") (pin "2") (pinfunction "2_2") (pintype "passive"))
      (node (ref "R81") (pin "1") (pinfunction "1_1") (pintype "passive"))
      (node (ref "SV1") (pin "29") (pinfunction "29_29") (pintype "passive"))
    )
    (net (code "151") (name "Y1") (class "Default")
      (node (ref "OR_1") (pin "3") (pinfunction "Y1_3") (pintype "output"))
      (node (ref "R63") (pin "2") (pinfunction "2_2") (pintype "passive"))
    )
    (net (code "152") (name "Y2") (class "Default")
      (node (ref "OR_1") (pin "6") (pinfunction "Y2_6") (pintype "output"))
      (node (ref "R64") (pin "2") (pinfunction "2_2") (pintype "passive"))
    )
    (net (code "153") (name "Y3") (class "Default")
      (node (ref "OR_1") (pin "8") (pinfunction "Y3_8") (pintype "output"))
      (node (ref "R62") (pin "2") (pinfunction "2_2") (pintype "passive"))
    )
    (net (code "154") (name "Y4") (class "Default")
      (node (ref "OR_1") (pin "11") (pinfunction "Y4_11") (pintype "output"))
      (node (ref "R61") (pin "2") (pinfunction "2_2") (pintype "passive"))
    )
    (net (code "155") (name "Y5") (class "Default")
      (node (ref "OR_2") (pin "3") (pinfunction "Y1_3") (pintype "output"))
      (node (ref "R68") (pin "2") (pinfunction "2_2") (pintype "passive"))
    )
    (net (code "156") (name "Y6") (class "Default")
      (node (ref "OR_2") (pin "6") (pinfunction "Y2_6") (pintype "output"))
      (node (ref "R67") (pin "2") (pinfunction "2_2") (pintype "passive"))
    )
    (net (code "157") (name "Y7") (class "Default")
      (node (ref "OR_2") (pin "8") (pinfunction "Y3_8") (pintype "output"))
      (node (ref "R66") (pin "2") (pinfunction "2_2") (pintype "passive"))
    )
    (net (code "158") (name "Y8") (class "Default")
      (node (ref "OR_2") (pin "11") (pinfunction "Y4_11") (pintype "output"))
      (node (ref "R65") (pin "2") (pinfunction "2_2") (pintype "passive"))
    )
    (net (code "159") (name "Y9") (class "Default")
      (node (ref "OR_3") (pin "3") (pinfunction "Y1_3") (pintype "output"))
      (node (ref "R72") (pin "2") (pinfunction "2_2") (pintype "passive"))
    )
    (net (code "160") (name "Y10") (class "Default")
      (node (ref "OR_3") (pin "6") (pinfunction "Y2_6") (pintype "output"))
      (node (ref "R71") (pin "2") (pinfunction "2_2") (pintype "passive"))
    )
    (net (code "161") (name "Y11") (class "Default")
      (node (ref "OR_3") (pin "8") (pinfunction "Y3_8") (pintype "output"))
      (node (ref "R70") (pin "2") (pinfunction "2_2") (pintype "passive"))
    )
    (net (code "162") (name "Y12") (class "Default")
      (node (ref "OR_3") (pin "11") (pinfunction "Y4_11") (pintype "output"))
      (node (ref "R69") (pin "2") (pinfunction "2_2") (pintype "passive"))
    )
    (net (code "163") (name "Y13") (class "Default")
      (node (ref "OR_4") (pin "3") (pinfunction "Y1_3") (pintype "output"))
      (node (ref "R76") (pin "2") (pinfunction "2_2") (pintype "passive"))
    )
    (net (code "164") (name "Y14") (class "Default")
      (node (ref "OR_4") (pin "6") (pinfunction "Y2_6") (pintype "output"))
      (node (ref "R75") (pin "2") (pinfunction "2_2") (pintype "passive"))
    )
    (net (code "165") (name "Y15") (class "Default")
      (node (ref "OR_4") (pin "8") (pinfunction "Y3_8") (pintype "output"))
      (node (ref "R74") (pin "2") (pinfunction "2_2") (pintype "passive"))
    )
    (net (code "166") (name "unconnected-(MAIN_POWER-1-OFF-Pad1)") (class "Default")
      (node (ref "MAIN_POWER") (pin "1") (pinfunction "1-OFF_1") (pintype "passive"))
    )
    (net (code "167") (name "unconnected-(OR_4-A4-Pad12)") (class "Default")
      (node (ref "OR_4") (pin "12") (pinfunction "A4_12") (pintype "input"))
    )
    (net (code "168") (name "unconnected-(OR_4-B4-Pad13)") (class "Default")
      (node (ref "OR_4") (pin "13") (pinfunction "B4_13") (pintype "input"))
    )
    (net (code "169") (name "unconnected-(OR_4-Y4-Pad11)") (class "Default")
      (node (ref "OR_4") (pin "11") (pinfunction "Y4_11") (pintype "output"))
    )
    (net (code "170") (name "unconnected-(OR_6-A4-Pad12)") (class "Default")
      (node (ref "OR_6") (pin "12") (pinfunction "A4_12") (pintype "input"))
    )
    (net (code "171") (name "unconnected-(OR_6-B4-Pad13)") (class "Default")
      (node (ref "OR_6") (pin "13") (pinfunction "B4_13") (pintype "input"))
    )
    (net (code "172") (name "unconnected-(OR_6-Y4-Pad11)") (class "Default")
      (node (ref "OR_6") (pin "11") (pinfunction "Y4_11") (pintype "output"))
    )
  )
)
